# STM_Board.net
KiCad netlist of a schematic drawn in EAGLE
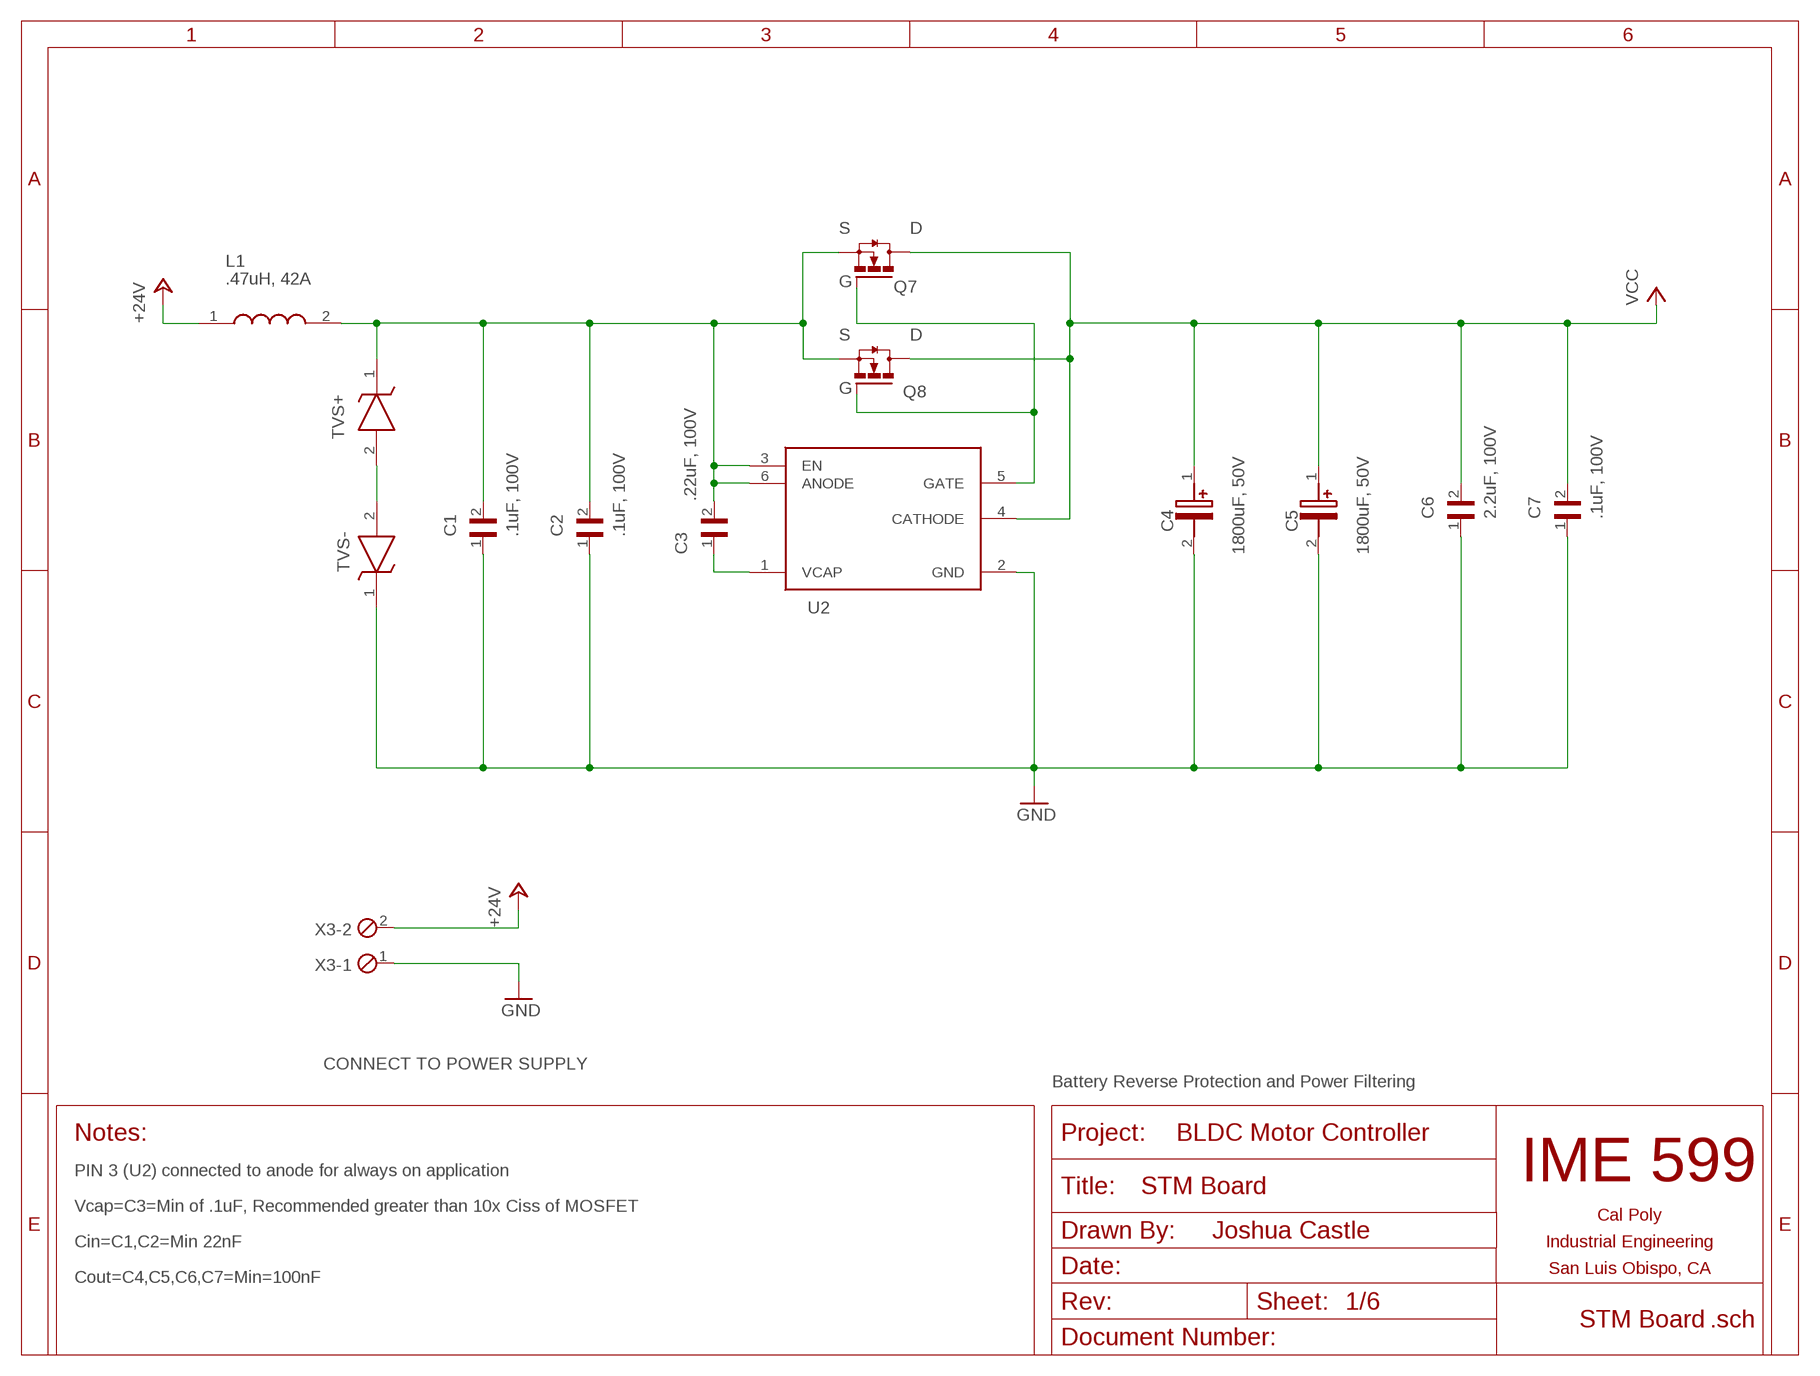
[diagram p0: schematic, sheet 1]
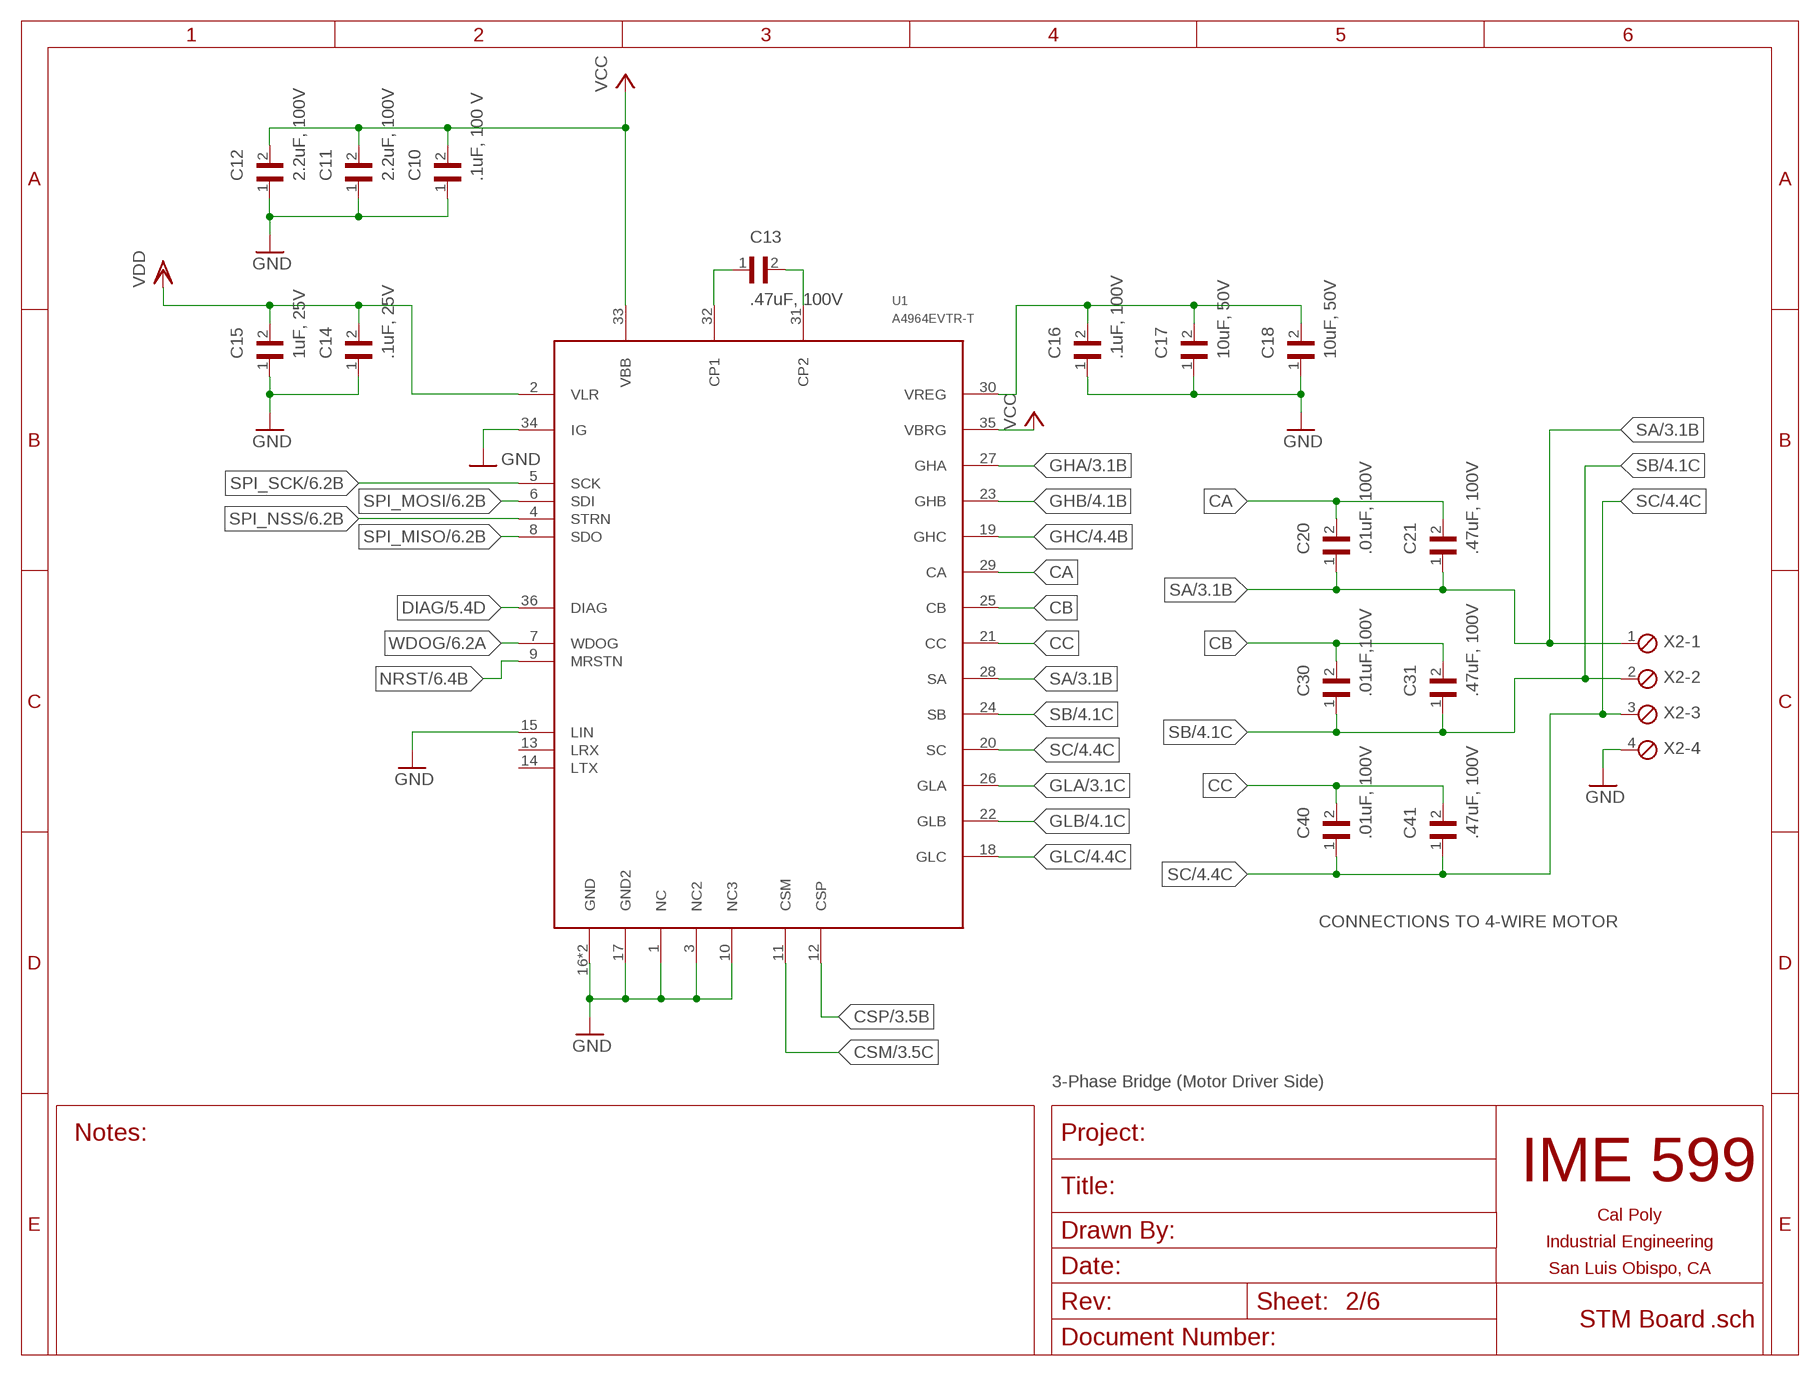
[diagram p1: schematic, sheet 2]
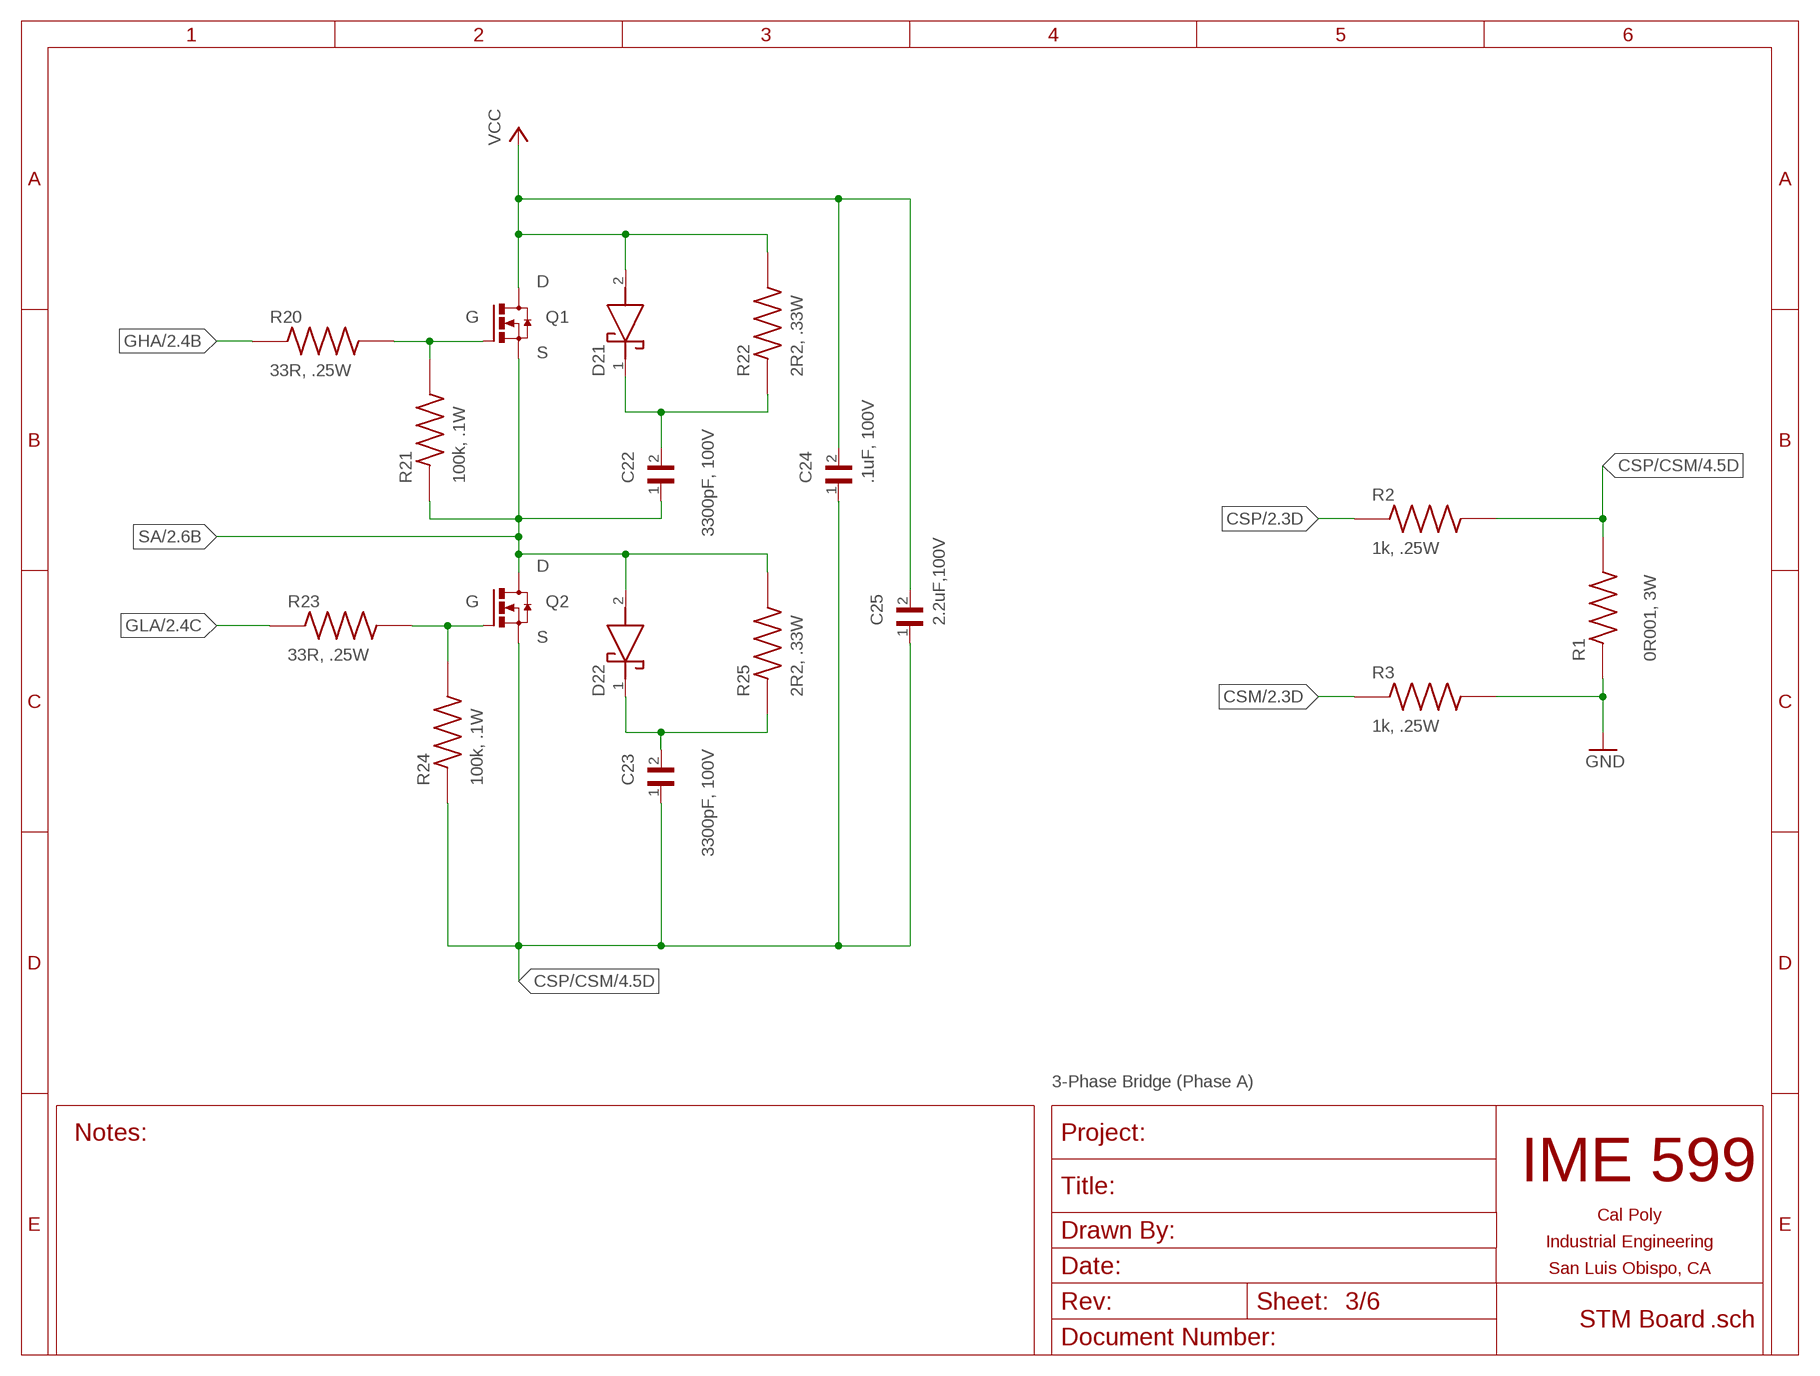
[diagram p2: schematic, sheet 3]
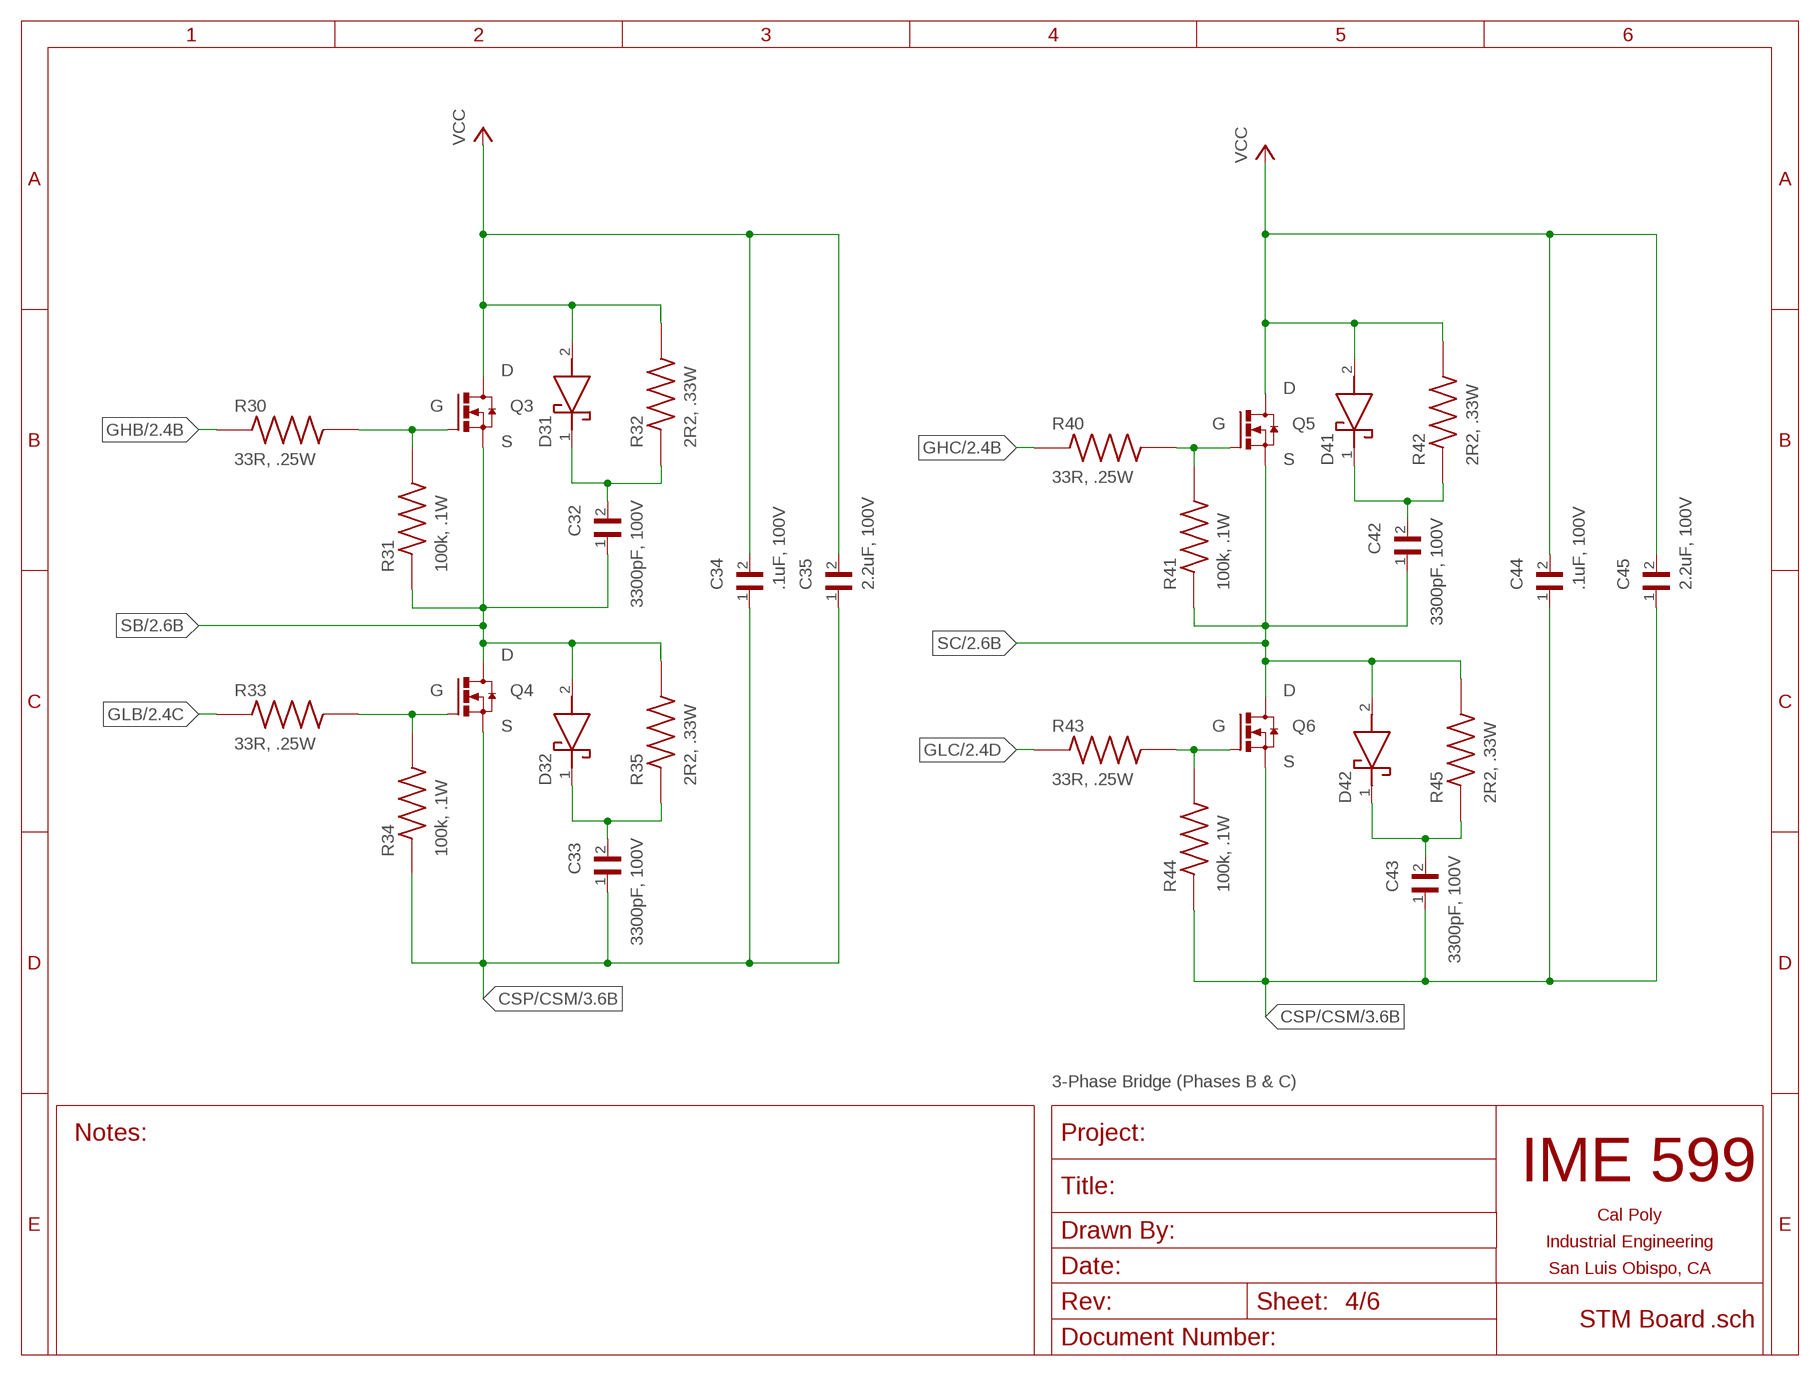
[diagram p3: schematic, sheet 4]
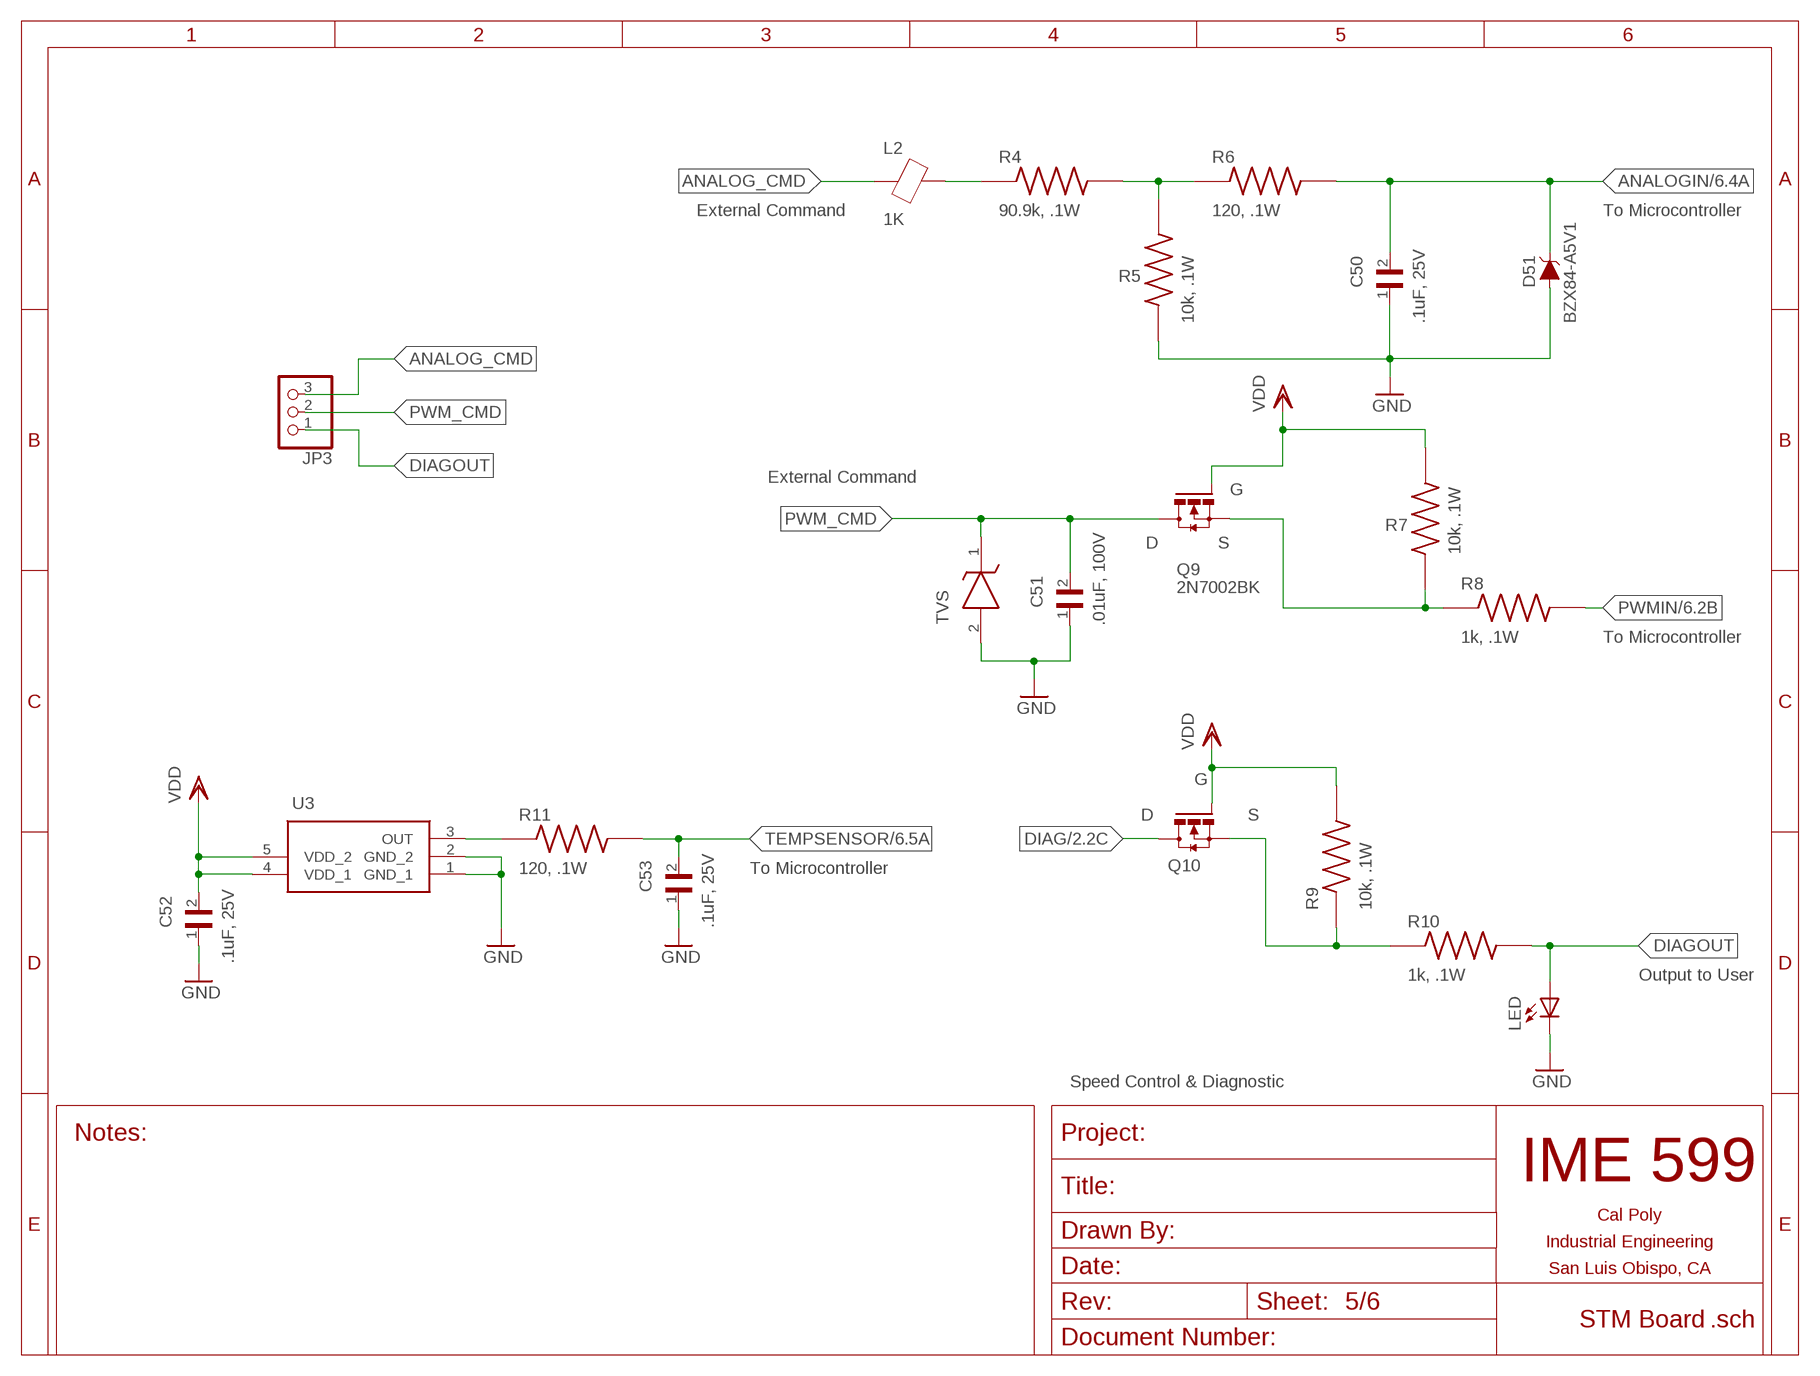
[diagram p4: schematic, sheet 5]
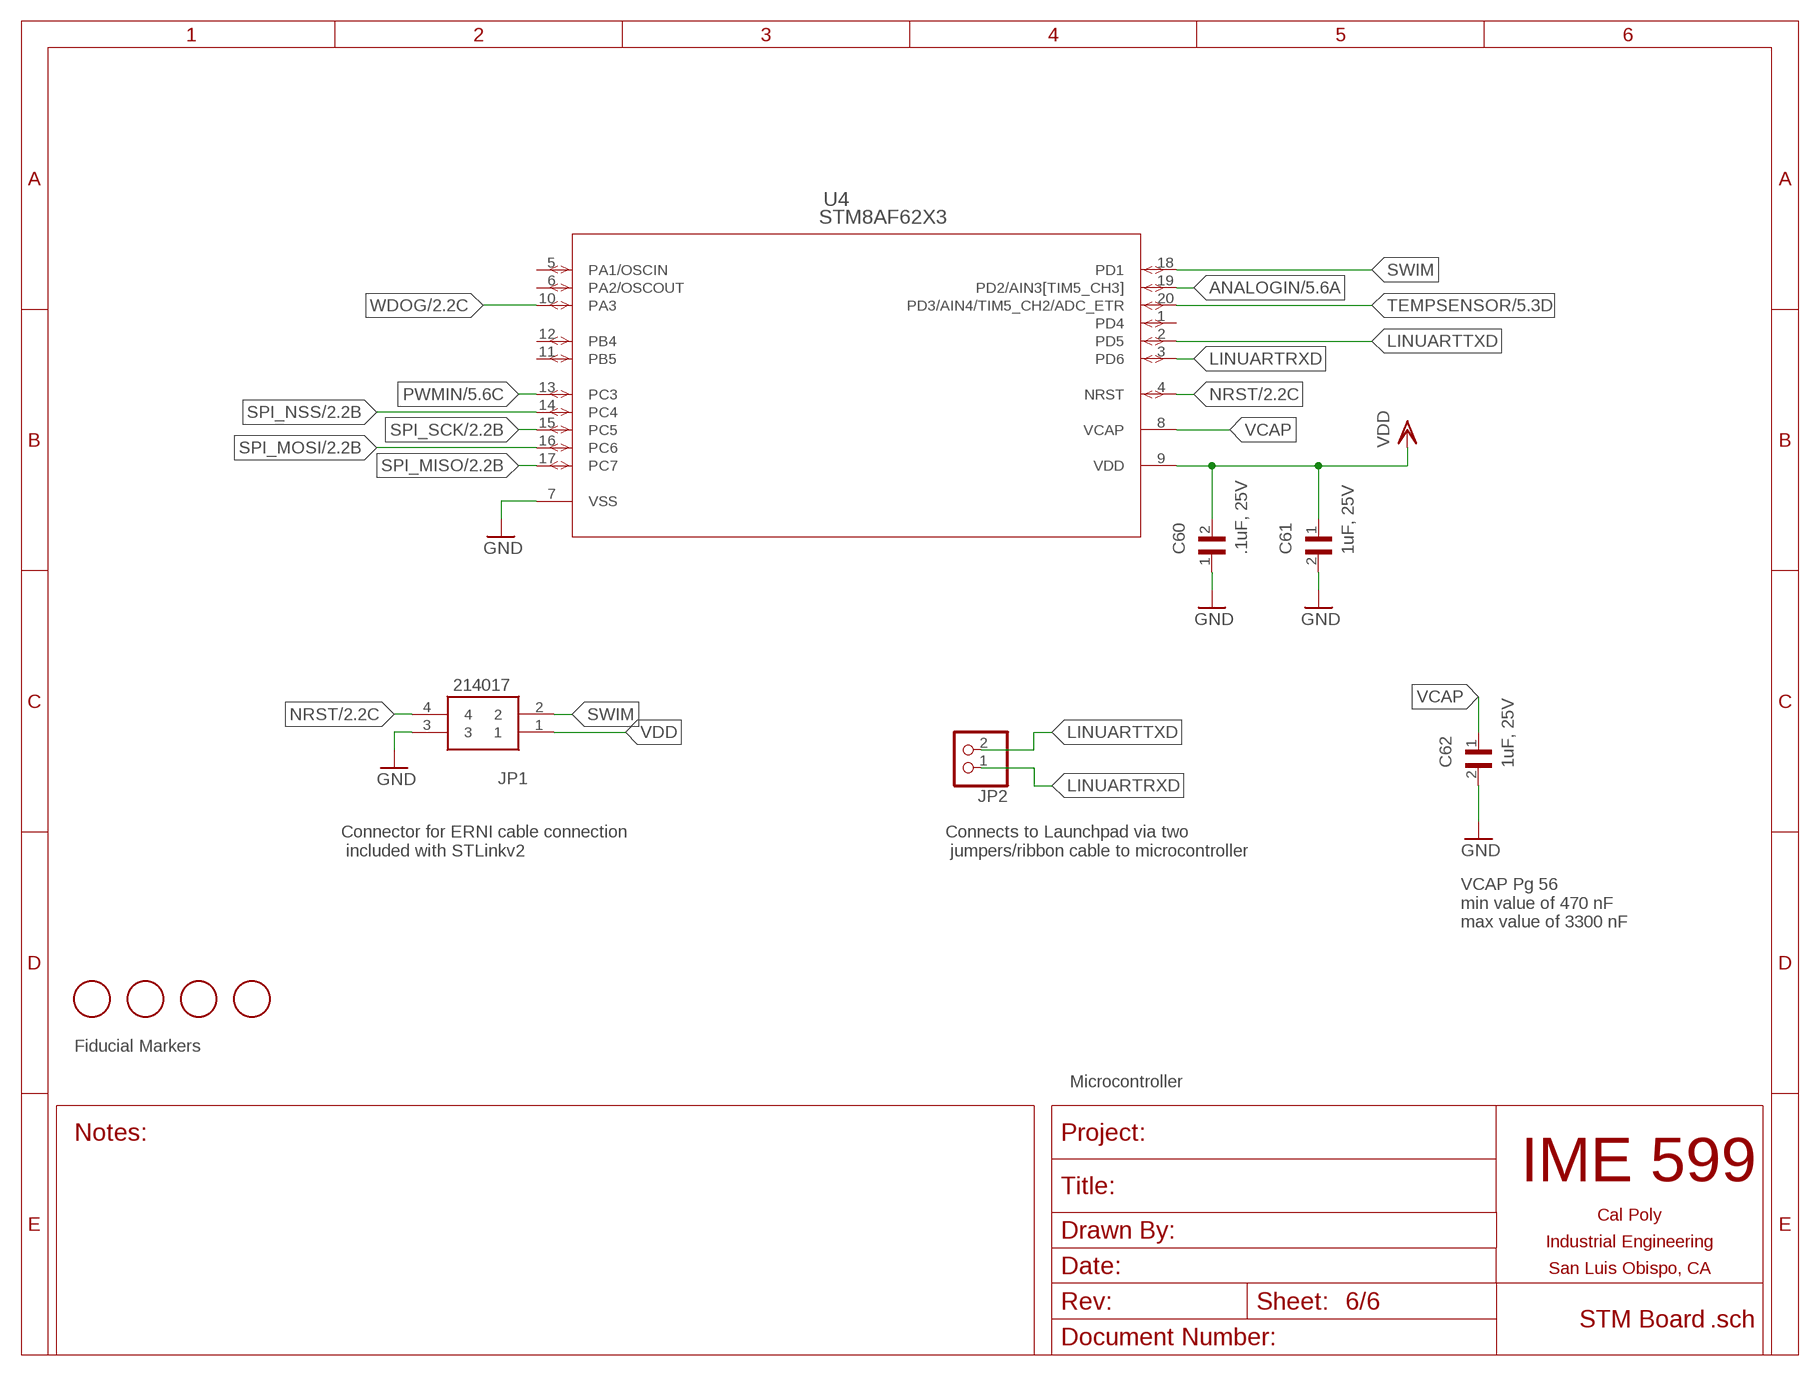
[diagram p5: schematic, sheet 6]

(export (version "E")
  (design (tool "Eeschema 10.0.6"))
  (components
    (comp (ref "C32")
      (value "3300pF, 100V")
      (footprint "eagle-import:CAPC1608X90N")
      (fields
        (field (name "DIGI-KEY_PART_NUMBER") "490-14767-1-ND")
        (field (name "MF") "Murata")
        (field (name "MP") "GCM188R72A332KA37D")
      )
      (libsource (lib "eagle-import") (part "GCM188R72A332KA37D"))
    )
    (comp (ref "C33")
      (value "3300pF, 100V")
      (footprint "eagle-import:CAPC1608X90N")
      (fields
        (field (name "DIGI-KEY_PART_NUMBER") "490-14767-1-ND")
        (field (name "MF") "Murata")
        (field (name "MP") "GCM188R72A332KA37D")
      )
      (libsource (lib "eagle-import") (part "GCM188R72A332KA37D"))
    )
    (comp (ref "C34")
      (value ".1uF, 100V")
      (footprint "eagle-import:CAPC2012X145N")
      (fields
        (field (name "DIGI-KEY_PART_NUMBER") "445-5827-1-ND")
        (field (name "MF") "TDK")
        (field (name "MP") "CGA4J2X7R2A104K125AA")
      )
      (libsource (lib "eagle-import") (part "CGA4J2X7R2A104K125AA"))
    )
    (comp (ref "C35")
      (value "2.2uF, 100V")
      (footprint "eagle-import:CAPC3326X230N")
      (fields
        (field (name "DIGI-KEY_PART_NUMBER") "399-13378-1-ND")
        (field (name "MF") "KEMET")
        (field (name "MP") "C1210X225K1RACAUTO")
      )
      (libsource (lib "eagle-import") (part "C1210X225K1RACAUTO_C1210X225K1RACAUTO"))
    )
    (comp (ref "C42")
      (value "3300pF, 100V")
      (footprint "eagle-import:CAPC1608X90N")
      (fields
        (field (name "DIGI-KEY_PART_NUMBER") "490-14767-1-ND")
        (field (name "MF") "Murata")
        (field (name "MP") "GCM188R72A332KA37D")
      )
      (libsource (lib "eagle-import") (part "GCM188R72A332KA37D"))
    )
    (comp (ref "C43")
      (value "3300pF, 100V")
      (footprint "eagle-import:CAPC1608X90N")
      (fields
        (field (name "DIGI-KEY_PART_NUMBER") "490-14767-1-ND")
        (field (name "MF") "Murata")
        (field (name "MP") "GCM188R72A332KA37D")
      )
      (libsource (lib "eagle-import") (part "GCM188R72A332KA37D"))
    )
    (comp (ref "C44")
      (value ".1uF, 100V")
      (footprint "eagle-import:CAPC2012X145N")
      (fields
        (field (name "DIGI-KEY_PART_NUMBER") "445-5827-1-ND")
        (field (name "MF") "TDK")
        (field (name "MP") "CGA4J2X7R2A104K125AA")
      )
      (libsource (lib "eagle-import") (part "CGA4J2X7R2A104K125AA"))
    )
    (comp (ref "C45")
      (value "2.2uF, 100V")
      (footprint "eagle-import:CAPC3326X230N")
      (fields
        (field (name "DIGI-KEY_PART_NUMBER") "399-13378-1-ND")
        (field (name "MF") "KEMET")
        (field (name "MP") "C1210X225K1RACAUTO")
      )
      (libsource (lib "eagle-import") (part "C1210X225K1RACAUTO_C1210X225K1RACAUTO"))
    )
    (comp (ref "D31")
      (value "PMEG6010EP,115")
      (footprint "eagle-import:SODFL4725X110N")
      (fields (field (name "MOUSER_PART_NUMBER") "771-PMEG6010EP115"))
      (libsource (lib "eagle-import") (part "PMEG6010EP,115"))
    )
    (comp (ref "D32")
      (value "PMEG6010EP,115")
      (footprint "eagle-import:SODFL4725X110N")
      (fields (field (name "MOUSER_PART_NUMBER") "771-PMEG6010EP115"))
      (libsource (lib "eagle-import") (part "PMEG6010EP,115"))
    )
    (comp (ref "D41")
      (value "PMEG6010EP,115")
      (footprint "eagle-import:SODFL4725X110N")
      (fields (field (name "MOUSER_PART_NUMBER") "771-PMEG6010EP115"))
      (libsource (lib "eagle-import") (part "PMEG6010EP,115"))
    )
    (comp (ref "D42")
      (value "PMEG6010EP,115")
      (footprint "eagle-import:SODFL4725X110N")
      (fields (field (name "MOUSER_PART_NUMBER") "771-PMEG6010EP115"))
      (libsource (lib "eagle-import") (part "PMEG6010EP,115"))
    )
    (comp (ref "Q3")
      (value "NVMFS5C604NLAFT1G")
      (footprint "eagle-import:DFN5_5X6(SO-8FL)_CASE-488AA_IS")
      (fields (field (name "MOUSER_PART_NUMBER") "863-NVMFS5C604NLFT1G"))
      (libsource (lib "eagle-import") (part "NVMFS5C604NLAFT1G"))
    )
    (comp (ref "Q4")
      (value "NVMFS5C604NLAFT1G")
      (footprint "eagle-import:DFN5_5X6(SO-8FL)_CASE-488AA_IS")
      (fields (field (name "MOUSER_PART_NUMBER") "863-NVMFS5C604NLFT1G"))
      (libsource (lib "eagle-import") (part "NVMFS5C604NLAFT1G"))
    )
    (comp (ref "Q5")
      (value "NVMFS5C604NLAFT1G")
      (footprint "eagle-import:DFN5_5X6(SO-8FL)_CASE-488AA_IS")
      (fields (field (name "MOUSER_PART_NUMBER") "863-NVMFS5C604NLFT1G"))
      (libsource (lib "eagle-import") (part "NVMFS5C604NLAFT1G"))
    )
    (comp (ref "Q6")
      (value "NVMFS5C604NLAFT1G")
      (footprint "eagle-import:DFN5_5X6(SO-8FL)_CASE-488AA_IS")
      (fields (field (name "MOUSER_PART_NUMBER") "863-NVMFS5C604NLFT1G"))
      (libsource (lib "eagle-import") (part "NVMFS5C604NLAFT1G"))
    )
    (comp (ref "R30")
      (value "33R, .25W")
      (footprint "eagle-import:0805RES")
      (libsource (lib "eagle-import") (part "CRCW060333R0FKEAHP"))
    )
    (comp (ref "R31")
      (value "100k, .1W")
      (footprint "eagle-import:RESC1608X55N")
      (fields (field (name "MF") "Vishay Dale") (field (name "MP") "CRCW0603100KFKEAC"))
      (libsource (lib "eagle-import") (part "CRCW0603100KFKEA"))
    )
    (comp (ref "R32")
      (value "2R2, .33W")
      (footprint "eagle-import:RESC1608X55N")
      (fields
        (field (name "DIGI-KEY_PART_NUMBER") "2019-SG73P1JTTD2R20FTR-ND")
        (field (name "MF") "KOA Speer")
        (field (name "MP") "SG73P1JTTD2R20F")
      )
      (libsource (lib "eagle-import") (part "SG73P1JTTD2R20F"))
    )
    (comp (ref "R33")
      (value "33R, .25W")
      (footprint "eagle-import:0805RES")
      (libsource (lib "eagle-import") (part "CRCW060333R0FKEAHP"))
    )
    (comp (ref "R34")
      (value "100k, .1W")
      (footprint "eagle-import:RESC1608X55N")
      (fields (field (name "MF") "Vishay Dale") (field (name "MP") "CRCW0603100KFKEAC"))
      (libsource (lib "eagle-import") (part "CRCW0603100KFKEA"))
    )
    (comp (ref "R35")
      (value "2R2, .33W")
      (footprint "eagle-import:RESC1608X55N")
      (fields
        (field (name "DIGI-KEY_PART_NUMBER") "2019-SG73P1JTTD2R20FTR-ND")
        (field (name "MF") "KOA Speer")
        (field (name "MP") "SG73P1JTTD2R20F")
      )
      (libsource (lib "eagle-import") (part "SG73P1JTTD2R20F"))
    )
    (comp (ref "R40")
      (value "33R, .25W")
      (footprint "eagle-import:0805RES")
      (libsource (lib "eagle-import") (part "CRCW060333R0FKEAHP"))
    )
    (comp (ref "R41")
      (value "100k, .1W")
      (footprint "eagle-import:RESC1608X55N")
      (fields (field (name "MF") "Vishay Dale") (field (name "MP") "CRCW0603100KFKEAC"))
      (libsource (lib "eagle-import") (part "CRCW0603100KFKEA"))
    )
    (comp (ref "R42")
      (value "2R2, .33W")
      (footprint "eagle-import:RESC1608X55N")
      (fields
        (field (name "DIGI-KEY_PART_NUMBER") "2019-SG73P1JTTD2R20FTR-ND")
        (field (name "MF") "KOA Speer")
        (field (name "MP") "SG73P1JTTD2R20F")
      )
      (libsource (lib "eagle-import") (part "SG73P1JTTD2R20F"))
    )
    (comp (ref "R43")
      (value "33R, .25W")
      (footprint "eagle-import:0805RES")
      (libsource (lib "eagle-import") (part "CRCW060333R0FKEAHP"))
    )
    (comp (ref "R44")
      (value "100k, .1W")
      (footprint "eagle-import:RESC1608X55N")
      (fields (field (name "MF") "Vishay Dale") (field (name "MP") "CRCW0603100KFKEAC"))
      (libsource (lib "eagle-import") (part "CRCW0603100KFKEA"))
    )
    (comp (ref "R45")
      (value "2R2, .33W")
      (footprint "eagle-import:RESC1608X55N")
      (fields
        (field (name "DIGI-KEY_PART_NUMBER") "2019-SG73P1JTTD2R20FTR-ND")
        (field (name "MF") "KOA Speer")
        (field (name "MP") "SG73P1JTTD2R20F")
      )
      (libsource (lib "eagle-import") (part "SG73P1JTTD2R20F"))
    )
    (comp (ref "C50")
      (value ".1uF, 25V")
      (footprint "eagle-import:CAPC1608X90N")
      (fields
        (field (name "DIGI-KEY_PART_NUMBER") "445-5667-1-ND")
        (field (name "MF") "TDK")
        (field (name "MP") "CGA3E2X7R1E104K080AA")
      )
      (libsource (lib "eagle-import") (part "CGA3E2X7R1E104K080AA"))
    )
    (comp (ref "C51")
      (value ".01uF, 100V")
      (footprint "eagle-import:CAPC1608X90N")
      (fields (field (name "MF") "Murata") (field (name "MP") "GCM188R72A223KA37J"))
      (libsource (lib "eagle-import") (part "GCM188R72A223KA37J"))
    )
    (comp (ref "C52")
      (value ".1uF, 25V")
      (footprint "eagle-import:CAPC1608X90N")
      (fields
        (field (name "DIGI-KEY_PART_NUMBER") "445-5667-1-ND")
        (field (name "MF") "TDK")
        (field (name "MP") "CGA3E2X7R1E104K080AA")
      )
      (libsource (lib "eagle-import") (part "CGA3E2X7R1E104K080AA"))
    )
    (comp (ref "C53")
      (value ".1uF, 25V")
      (footprint "eagle-import:CAPC1608X90N")
      (fields
        (field (name "DIGI-KEY_PART_NUMBER") "445-5667-1-ND")
        (field (name "MF") "TDK")
        (field (name "MP") "CGA3E2X7R1E104K080AA")
      )
      (libsource (lib "eagle-import") (part "CGA3E2X7R1E104K080AA"))
    )
    (comp (ref "D51")
      (value "BZX84-A5V1")
      (footprint "eagle-import:SOT95P230X110-3N")
      (fields
        (field (name "FARNELL_PART_NUMBER") "2345405")
        (field (name "MANUFACTURER_PART_NUMBER") "BZX84-A5V1,215")
      )
      (libsource (lib "eagle-import") (part "BZX84-A5V1,215"))
    )
    (comp (ref "JP3")
      (value "PINHD-1X3")
      (footprint "eagle-import:1X03")
      (libsource (lib "eagle-import") (part "PINHD-1X3"))
    )
    (comp (ref "L2")
      (value "1K")
      (footprint "eagle-import:BEADC1608X95N")
      (libsource (lib "eagle-import") (part "KMZ1608RHR102ATD25"))
    )
    (comp (ref "LED")
      (value "LTST-C170KRKT")
      (footprint "eagle-import:DIOC200X125X110")
      (fields (field (name "DIGI-KEY_PART_NUMBER") "160-1415-1-ND") (field (name "MF") "Lite-On Inc."))
      (libsource (lib "eagle-import") (part "LTST-C170KRKT"))
    )
    (comp (ref "Q9")
      (value "2N7002BK")
      (footprint "eagle-import:2N7002BK")
      (libsource (lib "eagle-import") (part "2N002BK"))
    )
    (comp (ref "Q10")
      (value "BSS123N_H6327")
      (footprint "eagle-import:BSS123N_H6327")
      (libsource (lib "eagle-import") (part "BSS123N_H6327"))
    )
    (comp (ref "R4")
      (value "90.9k, .1W")
      (footprint "eagle-import:CAPC1608X90N")
      (libsource (lib "eagle-import") (part "CRCW060318K0FK"))
    )
    (comp (ref "R5")
      (value "10k, .1W")
      (footprint "eagle-import:CAPC1608X90N")
      (libsource (lib "eagle-import") (part "CRCW060322K0FK"))
    )
    (comp (ref "R6")
      (value "120, .1W")
      (footprint "eagle-import:CAPC1608X90N")
      (libsource (lib "eagle-import") (part "CRCW0603120RFK"))
    )
    (comp (ref "R7")
      (value "10k, .1W")
      (footprint "eagle-import:RESC1508X50N")
      (fields (field (name "MF") "Vishay Dale") (field (name "MP") "CRCW060310K0FKEB"))
      (libsource (lib "eagle-import") (part "CRCW060310K0FKEB"))
    )
    (comp (ref "R8")
      (value "1k, .1W")
      (footprint "eagle-import:RESC1508X50N")
      (fields (field (name "MF") "Vishay") (field (name "MP") "CRCW06031K00FKEA"))
      (libsource (lib "eagle-import") (part "CRCW06031K00FKEA"))
    )
    (comp (ref "R9")
      (value "10k, .1W")
      (footprint "eagle-import:RESC1508X50N")
      (fields (field (name "MF") "Vishay Dale") (field (name "MP") "CRCW060310K0FKEB"))
      (libsource (lib "eagle-import") (part "CRCW060310K0FKEB"))
    )
    (comp (ref "R10")
      (value "1k, .1W")
      (footprint "eagle-import:RESC1508X50N")
      (fields (field (name "MF") "Vishay") (field (name "MP") "CRCW06031K00FKEA"))
      (libsource (lib "eagle-import") (part "CRCW06031K00FKEA"))
    )
    (comp (ref "R11")
      (value "120, .1W")
      (footprint "eagle-import:CAPC1608X90N")
      (libsource (lib "eagle-import") (part "CRCW0603120RFK"))
    )
    (comp (ref "TVS")
      (value "SMBJ30AQ-13-F")
      (footprint "eagle-import:DIOM5336X250N")
      (fields (field (name "MOUSER_PART_NUMBER") "621-SMBJ30AQ-13-F"))
      (libsource (lib "eagle-import") (part "SMBJ30AQ-13-F"))
    )
    (comp (ref "U3")
      (value "LMT86QDCKRQ1")
      (footprint "eagle-import:SOT65P210X110-5N")
      (fields (field (name "MOUSER_PART_NUMBER") "595-LMT86QDCKRQ1"))
      (libsource (lib "eagle-import") (part "LMT86QDCKRQ1"))
    )
    (comp (ref "C60")
      (value ".1uF, 25V")
      (footprint "eagle-import:CAPC1608X90N")
      (fields
        (field (name "DIGI-KEY_PART_NUMBER") "445-5667-1-ND")
        (field (name "MF") "TDK")
        (field (name "MP") "CGA3E2X7R1E104K080AA")
      )
      (libsource (lib "eagle-import") (part "CGA3E2X7R1E104K080AA"))
    )
    (comp (ref "C61")
      (value "1uF, 25V")
      (footprint "eagle-import:CAPC2012X88N")
      (fields
        (field (name "DIGI-KEY_PART_NUMBER") "399-6929-1-ND")
        (field (name "MF") "KEMET")
        (field (name "MP") "C0805C105K3RACAUTO")
      )
      (libsource (lib "eagle-import") (part "C0805C105K3RACAUTO"))
    )
    (comp (ref "C62")
      (value "1uF, 25V")
      (footprint "eagle-import:CAPC2012X88N")
      (fields
        (field (name "DIGI-KEY_PART_NUMBER") "399-6929-1-ND")
        (field (name "MF") "KEMET")
        (field (name "MP") "C0805C105K3RACAUTO")
      )
      (libsource (lib "eagle-import") (part "C0805C105K3RACAUTO"))
    )
    (comp (ref "JP1")
      (value "214017")
      (footprint "eagle-import:214017")
      (fields (field (name "MOUSER_PART_NUMBER") "305-214017"))
      (libsource (lib "eagle-import") (part "214017"))
    )
    (comp (ref "JP2")
      (value "PINHD-1X2")
      (footprint "eagle-import:1X02")
      (libsource (lib "eagle-import") (part "PINHD-1X2"))
    )
    (comp (ref "U$1")
      (value "FIDUCIAL")
      (footprint "eagle-import:FIDUCIAL_1MM")
      (libsource (lib "eagle-import") (part "FIDUCIAL"))
    )
    (comp (ref "U$2")
      (value "FIDUCIAL")
      (footprint "eagle-import:FIDUCIAL_1MM")
      (libsource (lib "eagle-import") (part "FIDUCIAL"))
    )
    (comp (ref "U$3")
      (value "FIDUCIAL")
      (footprint "eagle-import:FIDUCIAL_1MM")
      (libsource (lib "eagle-import") (part "FIDUCIAL"))
    )
    (comp (ref "U$4")
      (value "FIDUCIAL")
      (footprint "eagle-import:FIDUCIAL_1MM")
      (libsource (lib "eagle-import") (part "FIDUCIAL"))
    )
    (comp (ref "U4")
      (value "STM8AF62X3")
      (footprint "eagle-import:TSSOP20")
      (fields (field (name "COPYRIGHT") "Copyright (C) 2016 Accelerated Designs. All rights reserved"))
      (libsource (lib "eagle-import") (part "STM8AF62X3"))
    )
    (comp (ref "C10")
      (value ".1uF, 100 V")
      (footprint "eagle-import:CAPC2012X145N")
      (fields
        (field (name "DIGI-KEY_PART_NUMBER") "445-5827-1-ND")
        (field (name "MF") "TDK")
        (field (name "MP") "CGA4J2X7R2A104K125AA")
      )
      (libsource (lib "eagle-import") (part "CGA4J2X7R2A104K125AA"))
    )
    (comp (ref "C11")
      (value "2.2uF, 100V")
      (footprint "eagle-import:CAPC3326X230N")
      (fields
        (field (name "DIGI-KEY_PART_NUMBER") "399-13378-1-ND")
        (field (name "MF") "KEMET")
        (field (name "MP") "C1210X225K1RACAUTO")
      )
      (libsource (lib "eagle-import") (part "C1210X225K1RACAUTO_C1210X225K1RACAUTO"))
    )
    (comp (ref "C12")
      (value "2.2uF, 100V")
      (footprint "eagle-import:CAPC3326X230N")
      (fields
        (field (name "DIGI-KEY_PART_NUMBER") "399-13378-1-ND")
        (field (name "MF") "KEMET")
        (field (name "MP") "C1210X225K1RACAUTO")
      )
      (libsource (lib "eagle-import") (part "C1210X225K1RACAUTO_C1210X225K1RACAUTO"))
    )
    (comp (ref "C13")
      (value ".47uF, 100V")
      (footprint "eagle-import:CAPC2012X140N")
      (fields
        (field (name "DIGI-KEY_PART_NUMBER") "478-10684-1-ND")
        (field (name "MF") "AVX")
        (field (name "MP") "08051C474K4T2A")
      )
      (libsource (lib "eagle-import") (part "08051C474K4T2A"))
    )
    (comp (ref "C14")
      (value ".1uF, 25V")
      (footprint "eagle-import:CAPC1608X90N")
      (fields
        (field (name "DIGI-KEY_PART_NUMBER") "445-5667-1-ND")
        (field (name "MF") "TDK")
        (field (name "MP") "CGA3E2X7R1E104K080AA")
      )
      (libsource (lib "eagle-import") (part "CGA3E2X7R1E104K080AA"))
    )
    (comp (ref "C15")
      (value "1uF, 25V")
      (footprint "eagle-import:CAPC2012X140N")
      (fields (field (name "MF") "Murata") (field (name "MP") "GCM21BR71H105KA03K"))
      (libsource (lib "eagle-import") (part "GCM21BR71H105KA03K"))
    )
    (comp (ref "C16")
      (value ".1uF, 100V")
      (footprint "eagle-import:CAPC2012X145N")
      (fields (field (name "MF") "TDK") (field (name "MP") "CGA4J2X7R1E474K125AA"))
      (libsource (lib "eagle-import") (part "CGA4J2X7R1E474K125AA"))
    )
    (comp (ref "C17")
      (value "10uF, 50V")
      (footprint "eagle-import:CAPC3225X280N")
      (fields
        (field (name "DIGI-KEY_PART_NUMBER") "587-6026-1-ND")
        (field (name "MF") "Taiyo Yuden")
        (field (name "MP") "UMJ325KB7106KMHP")
      )
      (libsource (lib "eagle-import") (part "UMJ325KB7106KMHP"))
    )
    (comp (ref "C18")
      (value "10uF, 50V")
      (footprint "eagle-import:CAPC3225X280N")
      (fields
        (field (name "DIGI-KEY_PART_NUMBER") "587-6026-1-ND")
        (field (name "MF") "Taiyo Yuden")
        (field (name "MP") "UMJ325KB7106KMHP")
      )
      (libsource (lib "eagle-import") (part "UMJ325KB7106KMHP"))
    )
    (comp (ref "C20")
      (value ".01uF, 100V")
      (footprint "eagle-import:CAPC1608X90N")
      (fields
        (field (name "DIGI-KEY_PART_NUMBER") "490-4781-1-ND")
        (field (name "MF") "Murata")
        (field (name "MP") "GCM188R72A103KA37D")
      )
      (libsource (lib "eagle-import") (part "GCM188R72A103KA37D"))
    )
    (comp (ref "C21")
      (value ".47uF, 100V")
      (footprint "eagle-import:CAPC2012X140N")
      (fields
        (field (name "DIGI-KEY_PART_NUMBER") "478-10684-1-ND")
        (field (name "MF") "AVX")
        (field (name "MP") "08051C474K4T2A")
      )
      (libsource (lib "eagle-import") (part "08051C474K4T2A"))
    )
    (comp (ref "C30")
      (value ".01uF,100V")
      (footprint "eagle-import:CAPC1608X90N")
      (fields
        (field (name "DIGI-KEY_PART_NUMBER") "490-4781-1-ND")
        (field (name "MF") "Murata")
        (field (name "MP") "GCM188R72A103KA37D")
      )
      (libsource (lib "eagle-import") (part "GCM188R72A103KA37D"))
    )
    (comp (ref "C31")
      (value ".47uF, 100V")
      (footprint "eagle-import:CAPC2012X140N")
      (fields
        (field (name "DIGI-KEY_PART_NUMBER") "478-10684-1-ND")
        (field (name "MF") "AVX")
        (field (name "MP") "08051C474K4T2A")
      )
      (libsource (lib "eagle-import") (part "08051C474K4T2A"))
    )
    (comp (ref "C40")
      (value ".01uF, 100V")
      (footprint "eagle-import:CAPC1608X90N")
      (fields
        (field (name "DIGI-KEY_PART_NUMBER") "490-4781-1-ND")
        (field (name "MF") "Murata")
        (field (name "MP") "GCM188R72A103KA37D")
      )
      (libsource (lib "eagle-import") (part "GCM188R72A103KA37D"))
    )
    (comp (ref "C41")
      (value ".47uF, 100V")
      (footprint "eagle-import:CAPC2012X140N")
      (fields
        (field (name "DIGI-KEY_PART_NUMBER") "478-10684-1-ND")
        (field (name "MF") "AVX")
        (field (name "MP") "08051C474K4T2A")
      )
      (libsource (lib "eagle-import") (part "08051C474K4T2A"))
    )
    (comp (ref "U1")
      (value "A4964EVTR-T")
      (footprint "eagle-import:A4964EVTR-T")
      (libsource (lib "eagle-import") (part "A4964EVTR-T"))
    )
    (comp (ref "X2")
      (value "SCREWTERM_4P_254")
      (footprint "eagle-import:4POL254")
      (libsource (lib "eagle-import") (part "SCREWTERM_4P_254"))
    )
    (comp (ref "C1")
      (value ".1uF, 100V")
      (footprint "eagle-import:CAPC2012X145N")
      (fields (field (name "MF") "TDK") (field (name "MP") "CGA4J2X7R1E474K125AA"))
      (libsource (lib "eagle-import") (part "CGA4J2X7R1E474K125AA"))
    )
    (comp (ref "C2")
      (value ".1uF, 100V")
      (footprint "eagle-import:CAPC2012X145N")
      (fields (field (name "MF") "TDK") (field (name "MP") "CGA4J2X7R1E474K125AA"))
      (libsource (lib "eagle-import") (part "CGA4J2X7R1E474K125AA"))
    )
    (comp (ref "C3")
      (value ".22uF, 100V")
      (footprint "eagle-import:CAPC2012X140N")
      (fields
        (field (name "DIGI-KEY_PART_NUMBER") "399-17890-1-ND")
        (field (name "MF") "KEMET")
        (field (name "MP") "C0805C224K1RECAUTO")
      )
      (libsource (lib "eagle-import") (part "C0805C224K1RECAUTO"))
    )
    (comp (ref "C4")
      (value "1800uF, 50V")
      (footprint "eagle-import:CAPPRD750W80D1475H4150(HORIZONTAL)")
      (libsource (lib "eagle-import") (part "EGPA500ELL182MU40S(HORIZONTAL)"))
    )
    (comp (ref "C5")
      (value "1800uF, 50V")
      (footprint "eagle-import:CAPPRD750W80D1475H4150(HORIZONTAL)")
      (libsource (lib "eagle-import") (part "EGPA500ELL182MU40S(HORIZONTAL)"))
    )
    (comp (ref "C6")
      (value "2.2uF, 100V")
      (footprint "eagle-import:CAPC3326X230N")
      (fields
        (field (name "DIGI-KEY_PART_NUMBER") "399-13378-1-ND")
        (field (name "MF") "KEMET")
        (field (name "MP") "C1210X225K1RACAUTO")
      )
      (libsource (lib "eagle-import") (part "C1210X225K1RACAUTO"))
    )
    (comp (ref "C7")
      (value ".1uF, 100V")
      (footprint "eagle-import:CAPC2012X145N")
      (fields
        (field (name "DIGI-KEY_PART_NUMBER") "445-5827-1-ND")
        (field (name "MF") "TDK")
        (field (name "MP") "CGA4J2X7R2A104K125AA")
      )
      (libsource (lib "eagle-import") (part "CGA4J2X7R2A104K125AA"))
    )
    (comp (ref "L1")
      (value ".47uH, 42A")
      (footprint "eagle-import:HCM1A1305V2R47R")
      (fields
        (field (name "MANUFACTURER_PART_NUMBER") "HCM1A1305V2-R47-R")
        (field (name "MOUSER_PART_NUMBER") "504-HCM1A1305V2R47-R")
      )
      (libsource (lib "eagle-import") (part "HCM1A1305V2-R47-R"))
    )
    (comp (ref "Q7")
      (value "FDBL86361-F085")
      (footprint "eagle-import:H-PSOF8L-11.68X9.80_1")
      (fields (field (name "MOUSER_PART_NUMBER") "512-FDBL86361F085"))
      (libsource (lib "eagle-import") (part "FDBL86361-F085"))
    )
    (comp (ref "Q8")
      (value "FDBL86361-F085")
      (footprint "eagle-import:H-PSOF8L-11.68X9.80_1")
      (fields (field (name "MOUSER_PART_NUMBER") "512-FDBL86361F085"))
      (libsource (lib "eagle-import") (part "FDBL86361-F085"))
    )
    (comp (ref "TVS+")
      (value "SMBJ58A-Q")
      (footprint "eagle-import:DIOM5436X244N")
      (fields (field (name "MOUSER_PART_NUMBER") "652-SMBJ58A-Q"))
      (libsource (lib "eagle-import") (part "SMBJ58A-Q"))
    )
    (comp (ref "TVS-")
      (value "SMBJ26A-Q")
      (footprint "eagle-import:DIOM5436X244N")
      (fields (field (name "MOUSER_PART_NUMBER") "652-SMBJ26A-Q"))
      (libsource (lib "eagle-import") (part "SMBJ26A-Q"))
    )
    (comp (ref "U2")
      (value "LM74700-Q1MKX-1_NOPB")
      (footprint "eagle-import:SOT95P280X145-6N")
      (fields (field (name "MANUFACTURER_PART_NUMBER") "LM74700-Q1MKX-1/NOPB"))
      (libsource (lib "eagle-import") (part "LM74700-Q1MKX-1_NOPB"))
    )
    (comp (ref "X3")
      (value "SCREWTERM_2P_254")
      (footprint "eagle-import:2POL254")
      (libsource (lib "eagle-import") (part "SCREWTERM_2P_254"))
    )
    (comp (ref "C22")
      (value "3300pF, 100V")
      (footprint "eagle-import:CAPC1608X90N")
      (fields
        (field (name "DIGI-KEY_PART_NUMBER") "490-14767-1-ND")
        (field (name "MF") "Murata")
        (field (name "MP") "GCM188R72A332KA37D")
      )
      (libsource (lib "eagle-import") (part "GCM188R72A332KA37D"))
    )
    (comp (ref "C23")
      (value "3300pF, 100V")
      (footprint "eagle-import:CAPC1608X90N")
      (fields
        (field (name "DIGI-KEY_PART_NUMBER") "490-14767-1-ND")
        (field (name "MF") "Murata")
        (field (name "MP") "GCM188R72A332KA37D")
      )
      (libsource (lib "eagle-import") (part "GCM188R72A332KA37D"))
    )
    (comp (ref "C24")
      (value ".1uF, 100V")
      (footprint "eagle-import:CAPC2012X145N")
      (fields (field (name "MF") "TDK") (field (name "MP") "CGA4J2X7R1E474K125AA"))
      (libsource (lib "eagle-import") (part "CGA4J2X7R1E474K125AA"))
    )
    (comp (ref "C25")
      (value "2.2uF,100V")
      (footprint "eagle-import:CAPC3326X230N")
      (fields
        (field (name "DIGI-KEY_PART_NUMBER") "399-13378-1-ND")
        (field (name "MF") "KEMET")
        (field (name "MP") "C1210X225K1RACAUTO")
      )
      (libsource (lib "eagle-import") (part "C1210X225K1RACAUTO_C1210X225K1RACAUTO"))
    )
    (comp (ref "D21")
      (value "PMEG6010EP,115")
      (footprint "eagle-import:SODFL4725X110N")
      (fields (field (name "MOUSER_PART_NUMBER") "771-PMEG6010EP115"))
      (libsource (lib "eagle-import") (part "PMEG6010EP,115"))
    )
    (comp (ref "D22")
      (value "PMEG6010EP,115")
      (footprint "eagle-import:SODFL4725X110N")
      (fields (field (name "MOUSER_PART_NUMBER") "771-PMEG6010EP115"))
      (libsource (lib "eagle-import") (part "PMEG6010EP,115"))
    )
    (comp (ref "Q1")
      (value "NVMFS5C604NLAFT1G")
      (footprint "eagle-import:DFN5_5X6(SO-8FL)_CASE-488AA_IS")
      (fields (field (name "MOUSER_PART_NUMBER") "863-NVMFS5C604NLFT1G"))
      (libsource (lib "eagle-import") (part "NVMFS5C604NLAFT1G"))
    )
    (comp (ref "Q2")
      (value "NVMFS5C604NLAFT1G")
      (footprint "eagle-import:DFN5_5X6(SO-8FL)_CASE-488AA_IS")
      (fields (field (name "MOUSER_PART_NUMBER") "863-NVMFS5C604NLFT1G"))
      (libsource (lib "eagle-import") (part "NVMFS5C604NLAFT1G"))
    )
    (comp (ref "R1")
      (value "0R001, 3W")
      (footprint "eagle-import:RESC6432X90N")
      (fields
        (field (name "DIGI-KEY_PART_NUMBER") "CRA2512-FZ-R100ELFCT-ND")
        (field (name "MF") "Bourns")
        (field (name "MP") "CRA2512-FZ-R100ELF")
      )
      (libsource (lib "eagle-import") (part "CRA2512-FZ-R100ELF"))
    )
    (comp (ref "R2")
      (value "1k, .25W")
      (footprint "eagle-import:RESC1608X55N")
      (fields (field (name "MF") "Rohm") (field (name "MP") "ESR03EZPF1001"))
      (libsource (lib "eagle-import") (part "ESR03EZPF1001"))
    )
    (comp (ref "R3")
      (value "1k, .25W")
      (footprint "eagle-import:RESC1608X55N")
      (fields (field (name "MF") "Rohm") (field (name "MP") "ESR03EZPF1001"))
      (libsource (lib "eagle-import") (part "ESR03EZPF1001"))
    )
    (comp (ref "R20")
      (value "33R, .25W")
      (footprint "eagle-import:0805RES")
      (libsource (lib "eagle-import") (part "CRCW060333R0FKEAHP"))
    )
    (comp (ref "R21")
      (value "100k, .1W")
      (footprint "eagle-import:RESC1508X50N")
      (fields (field (name "MF") "Vishay") (field (name "MP") "CRCW06031K00FKEA"))
      (libsource (lib "eagle-import") (part "CRCW06031K00FKEA"))
    )
    (comp (ref "R22")
      (value "2R2, .33W")
      (footprint "eagle-import:RESC1608X55N")
      (fields
        (field (name "DIGI-KEY_PART_NUMBER") "2019-SG73P1JTTD2R20FTR-ND")
        (field (name "MF") "KOA Speer")
        (field (name "MP") "SG73P1JTTD2R20F")
      )
      (libsource (lib "eagle-import") (part "SG73P1JTTD2R20F"))
    )
    (comp (ref "R23")
      (value "33R, .25W")
      (footprint "eagle-import:0805RES")
      (libsource (lib "eagle-import") (part "CRCW060333R0FKEAHP"))
    )
    (comp (ref "R24")
      (value "100k, .1W")
      (footprint "eagle-import:RESC1508X50N")
      (fields (field (name "MF") "Vishay") (field (name "MP") "CRCW06031K00FKEA"))
      (libsource (lib "eagle-import") (part "CRCW06031K00FKEA"))
    )
    (comp (ref "R25")
      (value "2R2, .33W")
      (footprint "eagle-import:RESC1608X55N")
      (fields
        (field (name "DIGI-KEY_PART_NUMBER") "2019-SG73P1JTTD2R20FTR-ND")
        (field (name "MF") "KOA Speer")
        (field (name "MP") "SG73P1JTTD2R20F")
      )
      (libsource (lib "eagle-import") (part "SG73P1JTTD2R20F"))
    )
  )
  (nets
    (net (code "1") (name "+24V") (class "Default")
      (node (ref "L1") (pin "1") (pinfunction "1_1") (pintype "bidirectional"))
      (node (ref "X3") (pin "2") (pinfunction "1_2") (pintype "passive"))
    )
    (net (code "2") (name "ANALOGIN") (class "Default")
      (node (ref "C50") (pin "2") (pinfunction "2_2") (pintype "passive"))
      (node (ref "D51") (pin "3") (pinfunction "C_3") (pintype "passive"))
      (node (ref "R6") (pin "2") (pinfunction "2_2") (pintype "passive"))
      (node (ref "U4") (pin "19") (pinfunction "PD2/AIN3[TIM5_CH3]_19") (pintype "bidirectional"))
    )
    (net (code "3") (name "ANALOG_CMD") (class "Default")
      (node (ref "JP3") (pin "3") (pinfunction "3_3") (pintype "passive"))
      (node (ref "L2") (pin "1") (pinfunction "1_1") (pintype "bidirectional"))
    )
    (net (code "4") (name "CA") (class "Default")
      (node (ref "C20") (pin "2") (pinfunction "2_2") (pintype "passive"))
      (node (ref "C21") (pin "2") (pinfunction "2_2") (pintype "passive"))
      (node (ref "U1") (pin "29") (pinfunction "CA_29") (pintype "bidirectional"))
    )
    (net (code "5") (name "CB") (class "Default")
      (node (ref "C30") (pin "2") (pinfunction "2_2") (pintype "passive"))
      (node (ref "C31") (pin "2") (pinfunction "2_2") (pintype "passive"))
      (node (ref "U1") (pin "25") (pinfunction "CB_25") (pintype "bidirectional"))
    )
    (net (code "6") (name "CC") (class "Default")
      (node (ref "C40") (pin "2") (pinfunction "2_2") (pintype "passive"))
      (node (ref "C41") (pin "2") (pinfunction "2_2") (pintype "passive"))
      (node (ref "U1") (pin "21") (pinfunction "CC_21") (pintype "bidirectional"))
    )
    (net (code "7") (name "CSM") (class "Default")
      (node (ref "R3") (pin "1") (pinfunction "1_1") (pintype "passive"))
      (node (ref "U1") (pin "11") (pinfunction "CSM_11") (pintype "bidirectional"))
    )
    (net (code "8") (name "CSP") (class "Default")
      (node (ref "R2") (pin "1") (pinfunction "1_1") (pintype "passive"))
      (node (ref "U1") (pin "12") (pinfunction "CSP_12") (pintype "bidirectional"))
    )
    (net (code "9") (name "CSP{slash}CSM") (class "Default")
      (node (ref "C23") (pin "1") (pinfunction "1_1") (pintype "passive"))
      (node (ref "C24") (pin "1") (pinfunction "1_1") (pintype "passive"))
      (node (ref "C25") (pin "1") (pinfunction "1_1") (pintype "passive"))
      (node (ref "C33") (pin "1") (pinfunction "1_1") (pintype "passive"))
      (node (ref "C34") (pin "1") (pinfunction "1_1") (pintype "passive"))
      (node (ref "C35") (pin "1") (pinfunction "1_1") (pintype "passive"))
      (node (ref "C43") (pin "1") (pinfunction "1_1") (pintype "passive"))
      (node (ref "C44") (pin "1") (pinfunction "1_1") (pintype "passive"))
      (node (ref "C45") (pin "1") (pinfunction "1_1") (pintype "passive"))
      (node (ref "Q2") (pin "1") (pinfunction "S_1") (pintype "passive"))
      (node (ref "Q2") (pin "2") (pinfunction "S_2") (pintype "passive"))
      (node (ref "Q2") (pin "3") (pinfunction "S_3") (pintype "passive"))
      (node (ref "Q4") (pin "1") (pinfunction "S_1") (pintype "passive"))
      (node (ref "Q4") (pin "2") (pinfunction "S_2") (pintype "passive"))
      (node (ref "Q4") (pin "3") (pinfunction "S_3") (pintype "passive"))
      (node (ref "Q6") (pin "1") (pinfunction "S_1") (pintype "passive"))
      (node (ref "Q6") (pin "2") (pinfunction "S_2") (pintype "passive"))
      (node (ref "Q6") (pin "3") (pinfunction "S_3") (pintype "passive"))
      (node (ref "R1") (pin "2") (pinfunction "2_2") (pintype "passive"))
      (node (ref "R2") (pin "2") (pinfunction "2_2") (pintype "passive"))
      (node (ref "R24") (pin "1") (pinfunction "1_1") (pintype "passive"))
      (node (ref "R34") (pin "1") (pinfunction "1_1") (pintype "passive"))
      (node (ref "R44") (pin "1") (pinfunction "1_1") (pintype "passive"))
    )
    (net (code "10") (name "DIAG") (class "Default")
      (node (ref "Q10") (pin "3") (pinfunction "D_3") (pintype "passive"))
      (node (ref "U1") (pin "36") (pinfunction "DIAG_36") (pintype "bidirectional"))
    )
    (net (code "11") (name "DIAGOUT") (class "Default")
      (node (ref "JP3") (pin "1") (pinfunction "1_1") (pintype "passive"))
      (node (ref "LED") (pin "+") (pinfunction "+_+") (pintype "passive"))
      (node (ref "R10") (pin "2") (pinfunction "2_2") (pintype "passive"))
    )
    (net (code "12") (name "GHA") (class "Default")
      (node (ref "R20") (pin "1") (pinfunction "1_1") (pintype "passive"))
      (node (ref "U1") (pin "27") (pinfunction "GHA_27") (pintype "bidirectional"))
    )
    (net (code "13") (name "GHB") (class "Default")
      (node (ref "R30") (pin "1") (pinfunction "1_1") (pintype "passive"))
      (node (ref "U1") (pin "23") (pinfunction "GHB_23") (pintype "bidirectional"))
    )
    (net (code "14") (name "GHC") (class "Default")
      (node (ref "R40") (pin "1") (pinfunction "1_1") (pintype "passive"))
      (node (ref "U1") (pin "19") (pinfunction "GHC_19") (pintype "bidirectional"))
    )
    (net (code "15") (name "GLA") (class "Default")
      (node (ref "R23") (pin "1") (pinfunction "1_1") (pintype "passive"))
      (node (ref "U1") (pin "26") (pinfunction "GLA_26") (pintype "bidirectional"))
    )
    (net (code "16") (name "GLB") (class "Default")
      (node (ref "R33") (pin "1") (pinfunction "1_1") (pintype "passive"))
      (node (ref "U1") (pin "22") (pinfunction "GLB_22") (pintype "bidirectional"))
    )
    (net (code "17") (name "GLC") (class "Default")
      (node (ref "R43") (pin "1") (pinfunction "1_1") (pintype "passive"))
      (node (ref "U1") (pin "18") (pinfunction "GLC_18") (pintype "bidirectional"))
    )
    (net (code "18") (name "GND") (class "Default")
      (node (ref "C1") (pin "1") (pinfunction "1_1") (pintype "passive"))
      (node (ref "C10") (pin "1") (pinfunction "1_1") (pintype "passive"))
      (node (ref "C11") (pin "1") (pinfunction "1_1") (pintype "passive"))
      (node (ref "C12") (pin "1") (pinfunction "1_1") (pintype "passive"))
      (node (ref "C14") (pin "1") (pinfunction "1_1") (pintype "passive"))
      (node (ref "C15") (pin "1") (pinfunction "1_1") (pintype "passive"))
      (node (ref "C16") (pin "1") (pinfunction "1_1") (pintype "passive"))
      (node (ref "C17") (pin "1") (pinfunction "1_1") (pintype "passive"))
      (node (ref "C18") (pin "1") (pinfunction "1_1") (pintype "passive"))
      (node (ref "C2") (pin "1") (pinfunction "1_1") (pintype "passive"))
      (node (ref "C4") (pin "2") (pinfunction "-_2") (pintype "bidirectional"))
      (node (ref "C5") (pin "2") (pinfunction "-_2") (pintype "bidirectional"))
      (node (ref "C50") (pin "1") (pinfunction "1_1") (pintype "passive"))
      (node (ref "C51") (pin "1") (pinfunction "1_1") (pintype "passive"))
      (node (ref "C52") (pin "1") (pinfunction "1_1") (pintype "passive"))
      (node (ref "C53") (pin "1") (pinfunction "1_1") (pintype "passive"))
      (node (ref "C6") (pin "1") (pinfunction "1_1") (pintype "passive"))
      (node (ref "C60") (pin "1") (pinfunction "1_1") (pintype "passive"))
      (node (ref "C61") (pin "2") (pinfunction "2_2") (pintype "passive"))
      (node (ref "C62") (pin "2") (pinfunction "2_2") (pintype "passive"))
      (node (ref "C7") (pin "1") (pinfunction "1_1") (pintype "passive"))
      (node (ref "D51") (pin "1") (pinfunction "A_1") (pintype "passive"))
      (node (ref "D51") (pin "2") (pinfunction "A_2") (pintype "passive"))
      (node (ref "JP1") (pin "3") (pinfunction "3_3") (pintype "bidirectional"))
      (node (ref "LED") (pin "-") (pinfunction "-_-") (pintype "passive"))
      (node (ref "R1") (pin "1") (pinfunction "1_1") (pintype "passive"))
      (node (ref "R3") (pin "2") (pinfunction "2_2") (pintype "passive"))
      (node (ref "R5") (pin "1") (pinfunction "1_1") (pintype "passive"))
      (node (ref "TVS") (pin "2") (pinfunction "A_2") (pintype "bidirectional"))
      (node (ref "TVS-") (pin "1") (pinfunction "K_1") (pintype "bidirectional"))
      (node (ref "U1") (pin "1") (pinfunction "NC_1") (pintype "bidirectional"))
      (node (ref "U1") (pin "10") (pinfunction "NC3_10") (pintype "bidirectional"))
      (node (ref "U1") (pin "15") (pinfunction "LIN_15") (pintype "bidirectional"))
      (node (ref "U1") (pin "16") (pinfunction "GND_16") (pintype "bidirectional"))
      (node (ref "U1") (pin "17") (pinfunction "GND2_17") (pintype "bidirectional"))
      (node (ref "U1") (pin "3") (pinfunction "NC2_3") (pintype "bidirectional"))
      (node (ref "U1") (pin "34") (pinfunction "IG_34") (pintype "bidirectional"))
      (node (ref "U1") (pin "37") (pinfunction "GND_37") (pintype "bidirectional"))
      (node (ref "U2") (pin "2") (pinfunction "GND_2") (pintype "bidirectional"))
      (node (ref "U3") (pin "1") (pinfunction "GND_1_1") (pintype "bidirectional"))
      (node (ref "U3") (pin "2") (pinfunction "GND_2_2") (pintype "bidirectional"))
      (node (ref "U4") (pin "7") (pinfunction "VSS_7") (pintype "power_in"))
      (node (ref "X2") (pin "4") (pinfunction "1_4") (pintype "passive"))
      (node (ref "X3") (pin "1") (pinfunction "1_1") (pintype "passive"))
    )
    (net (code "19") (name "LINUARTRXD") (class "Default")
      (node (ref "JP2") (pin "1") (pinfunction "1_1") (pintype "passive"))
      (node (ref "U4") (pin "3") (pinfunction "PD6_3") (pintype "bidirectional"))
    )
    (net (code "20") (name "LINUARTTXD") (class "Default")
      (node (ref "JP2") (pin "2") (pinfunction "2_2") (pintype "passive"))
      (node (ref "U4") (pin "2") (pinfunction "PD5_2") (pintype "bidirectional"))
    )
    (net (code "21") (name "NRST") (class "Default")
      (node (ref "JP1") (pin "4") (pinfunction "4_4") (pintype "bidirectional"))
      (node (ref "U1") (pin "9") (pinfunction "MRSTN_9") (pintype "bidirectional"))
      (node (ref "U4") (pin "4") (pinfunction "NRST_4") (pintype "bidirectional"))
    )
    (net (code "22") (name "Net-(D21-K)") (class "Default")
      (node (ref "C22") (pin "2") (pinfunction "2_2") (pintype "passive"))
      (node (ref "D21") (pin "1") (pinfunction "K_1") (pintype "bidirectional"))
      (node (ref "R22") (pin "1") (pinfunction "1_1") (pintype "passive"))
    )
    (net (code "23") (name "Net-(D22-K)") (class "Default")
      (node (ref "C23") (pin "2") (pinfunction "2_2") (pintype "passive"))
      (node (ref "D22") (pin "1") (pinfunction "K_1") (pintype "bidirectional"))
      (node (ref "R25") (pin "1") (pinfunction "1_1") (pintype "passive"))
    )
    (net (code "24") (name "Net-(D31-K)") (class "Default")
      (node (ref "C32") (pin "2") (pinfunction "2_2") (pintype "passive"))
      (node (ref "D31") (pin "1") (pinfunction "K_1") (pintype "bidirectional"))
      (node (ref "R32") (pin "1") (pinfunction "1_1") (pintype "passive"))
    )
    (net (code "25") (name "Net-(D32-K)") (class "Default")
      (node (ref "C33") (pin "2") (pinfunction "2_2") (pintype "passive"))
      (node (ref "D32") (pin "1") (pinfunction "K_1") (pintype "bidirectional"))
      (node (ref "R35") (pin "1") (pinfunction "1_1") (pintype "passive"))
    )
    (net (code "26") (name "Net-(D41-K)") (class "Default")
      (node (ref "C42") (pin "2") (pinfunction "2_2") (pintype "passive"))
      (node (ref "D41") (pin "1") (pinfunction "K_1") (pintype "bidirectional"))
      (node (ref "R42") (pin "1") (pinfunction "1_1") (pintype "passive"))
    )
    (net (code "27") (name "Net-(D42-K)") (class "Default")
      (node (ref "C43") (pin "2") (pinfunction "2_2") (pintype "passive"))
      (node (ref "D42") (pin "1") (pinfunction "K_1") (pintype "bidirectional"))
      (node (ref "R45") (pin "1") (pinfunction "1_1") (pintype "passive"))
    )
    (net (code "28") (name "Net-(L2-Pad2)") (class "Default")
      (node (ref "L2") (pin "2") (pinfunction "2_2") (pintype "bidirectional"))
      (node (ref "R4") (pin "1") (pinfunction "1_1") (pintype "passive"))
    )
    (net (code "29") (name "Net-(Q1-G)") (class "Default")
      (node (ref "Q1") (pin "4") (pinfunction "G_4") (pintype "passive"))
      (node (ref "R20") (pin "2") (pinfunction "2_2") (pintype "passive"))
      (node (ref "R21") (pin "2") (pinfunction "2_2") (pintype "passive"))
    )
    (net (code "30") (name "Net-(Q2-G)") (class "Default")
      (node (ref "Q2") (pin "4") (pinfunction "G_4") (pintype "passive"))
      (node (ref "R23") (pin "2") (pinfunction "2_2") (pintype "passive"))
      (node (ref "R24") (pin "2") (pinfunction "2_2") (pintype "passive"))
    )
    (net (code "31") (name "Net-(Q3-G)") (class "Default")
      (node (ref "Q3") (pin "4") (pinfunction "G_4") (pintype "passive"))
      (node (ref "R30") (pin "2") (pinfunction "2_2") (pintype "passive"))
      (node (ref "R31") (pin "2") (pinfunction "2_2") (pintype "passive"))
    )
    (net (code "32") (name "Net-(Q4-G)") (class "Default")
      (node (ref "Q4") (pin "4") (pinfunction "G_4") (pintype "passive"))
      (node (ref "R33") (pin "2") (pinfunction "2_2") (pintype "passive"))
      (node (ref "R34") (pin "2") (pinfunction "2_2") (pintype "passive"))
    )
    (net (code "33") (name "Net-(Q5-G)") (class "Default")
      (node (ref "Q5") (pin "4") (pinfunction "G_4") (pintype "passive"))
      (node (ref "R40") (pin "2") (pinfunction "2_2") (pintype "passive"))
      (node (ref "R41") (pin "2") (pinfunction "2_2") (pintype "passive"))
    )
    (net (code "34") (name "Net-(Q6-G)") (class "Default")
      (node (ref "Q6") (pin "4") (pinfunction "G_4") (pintype "passive"))
      (node (ref "R43") (pin "2") (pinfunction "2_2") (pintype "passive"))
      (node (ref "R44") (pin "2") (pinfunction "2_2") (pintype "passive"))
    )
    (net (code "35") (name "Net-(Q7-G)") (class "Default")
      (node (ref "Q7") (pin "1") (pinfunction "G_1") (pintype "passive"))
      (node (ref "Q8") (pin "1") (pinfunction "G_1") (pintype "passive"))
      (node (ref "U2") (pin "5") (pinfunction "GATE_5") (pintype "bidirectional"))
    )
    (net (code "36") (name "Net-(Q9-S)") (class "Default")
      (node (ref "Q9") (pin "2") (pinfunction "S_2") (pintype "passive"))
      (node (ref "R7") (pin "1") (pinfunction "1_1") (pintype "passive"))
      (node (ref "R8") (pin "1") (pinfunction "1_1") (pintype "passive"))
    )
    (net (code "37") (name "Net-(Q10-S)") (class "Default")
      (node (ref "Q10") (pin "2") (pinfunction "S_2") (pintype "passive"))
      (node (ref "R10") (pin "1") (pinfunction "1_1") (pintype "passive"))
      (node (ref "R9") (pin "1") (pinfunction "1_1") (pintype "passive"))
    )
    (net (code "38") (name "Net-(R4-Pad2)") (class "Default")
      (node (ref "R4") (pin "2") (pinfunction "2_2") (pintype "passive"))
      (node (ref "R5") (pin "2") (pinfunction "2_2") (pintype "passive"))
      (node (ref "R6") (pin "1") (pinfunction "1_1") (pintype "passive"))
    )
    (net (code "39") (name "Net-(TVS+-A)") (class "Default")
      (node (ref "TVS+") (pin "2") (pinfunction "A_2") (pintype "bidirectional"))
      (node (ref "TVS-") (pin "2") (pinfunction "A_2") (pintype "bidirectional"))
    )
    (net (code "40") (name "Net-(TVS+-K)") (class "Default")
      (node (ref "C1") (pin "2") (pinfunction "2_2") (pintype "passive"))
      (node (ref "C2") (pin "2") (pinfunction "2_2") (pintype "passive"))
      (node (ref "C3") (pin "2") (pinfunction "2_2") (pintype "passive"))
      (node (ref "L1") (pin "2") (pinfunction "2_2") (pintype "bidirectional"))
      (node (ref "Q7") (pin "2") (pinfunction "S_2") (pintype "passive"))
      (node (ref "Q7") (pin "3") (pinfunction "S_3") (pintype "passive"))
      (node (ref "Q7") (pin "4") (pinfunction "S_4") (pintype "passive"))
      (node (ref "Q7") (pin "5") (pinfunction "S_5") (pintype "passive"))
      (node (ref "Q7") (pin "6") (pinfunction "S_6") (pintype "passive"))
      (node (ref "Q7") (pin "7") (pinfunction "S_7") (pintype "passive"))
      (node (ref "Q7") (pin "8") (pinfunction "S_8") (pintype "passive"))
      (node (ref "Q8") (pin "2") (pinfunction "S_2") (pintype "passive"))
      (node (ref "Q8") (pin "3") (pinfunction "S_3") (pintype "passive"))
      (node (ref "Q8") (pin "4") (pinfunction "S_4") (pintype "passive"))
      (node (ref "Q8") (pin "5") (pinfunction "S_5") (pintype "passive"))
      (node (ref "Q8") (pin "6") (pinfunction "S_6") (pintype "passive"))
      (node (ref "Q8") (pin "7") (pinfunction "S_7") (pintype "passive"))
      (node (ref "Q8") (pin "8") (pinfunction "S_8") (pintype "passive"))
      (node (ref "TVS+") (pin "1") (pinfunction "K_1") (pintype "bidirectional"))
      (node (ref "U2") (pin "3") (pinfunction "EN_3") (pintype "bidirectional"))
      (node (ref "U2") (pin "6") (pinfunction "ANODE_6") (pintype "bidirectional"))
    )
    (net (code "41") (name "Net-(U1-CP1)") (class "Default")
      (node (ref "C13") (pin "1") (pinfunction "1_1") (pintype "passive"))
      (node (ref "U1") (pin "32") (pinfunction "CP1_32") (pintype "bidirectional"))
    )
    (net (code "42") (name "Net-(U1-CP2)") (class "Default")
      (node (ref "C13") (pin "2") (pinfunction "2_2") (pintype "passive"))
      (node (ref "U1") (pin "31") (pinfunction "CP2_31") (pintype "bidirectional"))
    )
    (net (code "43") (name "Net-(U1-VREG)") (class "Default")
      (node (ref "C16") (pin "2") (pinfunction "2_2") (pintype "passive"))
      (node (ref "C17") (pin "2") (pinfunction "2_2") (pintype "passive"))
      (node (ref "C18") (pin "2") (pinfunction "2_2") (pintype "passive"))
      (node (ref "U1") (pin "30") (pinfunction "VREG_30") (pintype "bidirectional"))
    )
    (net (code "44") (name "Net-(U2-VCAP)") (class "Default")
      (node (ref "C3") (pin "1") (pinfunction "1_1") (pintype "passive"))
      (node (ref "U2") (pin "1") (pinfunction "VCAP_1") (pintype "bidirectional"))
    )
    (net (code "45") (name "Net-(U3-OUT)") (class "Default")
      (node (ref "R11") (pin "1") (pinfunction "1_1") (pintype "passive"))
      (node (ref "U3") (pin "3") (pinfunction "OUT_3") (pintype "bidirectional"))
    )
    (net (code "46") (name "PWMIN") (class "Default")
      (node (ref "R8") (pin "2") (pinfunction "2_2") (pintype "passive"))
      (node (ref "U4") (pin "13") (pinfunction "PC3_13") (pintype "bidirectional"))
    )
    (net (code "47") (name "PWM_CMD") (class "Default")
      (node (ref "C51") (pin "2") (pinfunction "2_2") (pintype "passive"))
      (node (ref "JP3") (pin "2") (pinfunction "2_2") (pintype "passive"))
      (node (ref "Q9") (pin "3") (pinfunction "D_3") (pintype "passive"))
      (node (ref "TVS") (pin "1") (pinfunction "K_1") (pintype "bidirectional"))
    )
    (net (code "48") (name "SA") (class "Default")
      (node (ref "C20") (pin "1") (pinfunction "1_1") (pintype "passive"))
      (node (ref "C21") (pin "1") (pinfunction "1_1") (pintype "passive"))
      (node (ref "C22") (pin "1") (pinfunction "1_1") (pintype "passive"))
      (node (ref "D22") (pin "2") (pinfunction "A_2") (pintype "bidirectional"))
      (node (ref "Q1") (pin "1") (pinfunction "S_1") (pintype "passive"))
      (node (ref "Q1") (pin "2") (pinfunction "S_2") (pintype "passive"))
      (node (ref "Q1") (pin "3") (pinfunction "S_3") (pintype "passive"))
      (node (ref "Q2") (pin "5") (pinfunction "D_5") (pintype "passive"))
      (node (ref "Q2") (pin "6") (pinfunction "D_6") (pintype "passive"))
      (node (ref "Q2") (pin "7") (pinfunction "D_7") (pintype "passive"))
      (node (ref "R21") (pin "1") (pinfunction "1_1") (pintype "passive"))
      (node (ref "R25") (pin "2") (pinfunction "2_2") (pintype "passive"))
      (node (ref "U1") (pin "28") (pinfunction "SA_28") (pintype "bidirectional"))
      (node (ref "X2") (pin "1") (pinfunction "1_1") (pintype "passive"))
    )
    (net (code "49") (name "SB") (class "Default")
      (node (ref "C30") (pin "1") (pinfunction "1_1") (pintype "passive"))
      (node (ref "C31") (pin "1") (pinfunction "1_1") (pintype "passive"))
      (node (ref "C32") (pin "1") (pinfunction "1_1") (pintype "passive"))
      (node (ref "D32") (pin "2") (pinfunction "A_2") (pintype "bidirectional"))
      (node (ref "Q3") (pin "1") (pinfunction "S_1") (pintype "passive"))
      (node (ref "Q3") (pin "2") (pinfunction "S_2") (pintype "passive"))
      (node (ref "Q3") (pin "3") (pinfunction "S_3") (pintype "passive"))
      (node (ref "Q4") (pin "5") (pinfunction "D_5") (pintype "passive"))
      (node (ref "Q4") (pin "6") (pinfunction "D_6") (pintype "passive"))
      (node (ref "Q4") (pin "7") (pinfunction "D_7") (pintype "passive"))
      (node (ref "R31") (pin "1") (pinfunction "1_1") (pintype "passive"))
      (node (ref "R35") (pin "2") (pinfunction "2_2") (pintype "passive"))
      (node (ref "U1") (pin "24") (pinfunction "SB_24") (pintype "bidirectional"))
      (node (ref "X2") (pin "2") (pinfunction "1_2") (pintype "passive"))
    )
    (net (code "50") (name "SC") (class "Default")
      (node (ref "C40") (pin "1") (pinfunction "1_1") (pintype "passive"))
      (node (ref "C41") (pin "1") (pinfunction "1_1") (pintype "passive"))
      (node (ref "C42") (pin "1") (pinfunction "1_1") (pintype "passive"))
      (node (ref "D42") (pin "2") (pinfunction "A_2") (pintype "bidirectional"))
      (node (ref "Q5") (pin "1") (pinfunction "S_1") (pintype "passive"))
      (node (ref "Q5") (pin "2") (pinfunction "S_2") (pintype "passive"))
      (node (ref "Q5") (pin "3") (pinfunction "S_3") (pintype "passive"))
      (node (ref "Q6") (pin "5") (pinfunction "D_5") (pintype "passive"))
      (node (ref "Q6") (pin "6") (pinfunction "D_6") (pintype "passive"))
      (node (ref "Q6") (pin "7") (pinfunction "D_7") (pintype "passive"))
      (node (ref "R41") (pin "1") (pinfunction "1_1") (pintype "passive"))
      (node (ref "R45") (pin "2") (pinfunction "2_2") (pintype "passive"))
      (node (ref "U1") (pin "20") (pinfunction "SC_20") (pintype "bidirectional"))
      (node (ref "X2") (pin "3") (pinfunction "1_3") (pintype "passive"))
    )
    (net (code "51") (name "SPI_MISO") (class "Default")
      (node (ref "U1") (pin "8") (pinfunction "SDO_8") (pintype "bidirectional"))
      (node (ref "U4") (pin "17") (pinfunction "PC7_17") (pintype "bidirectional"))
    )
    (net (code "52") (name "SPI_MOSI") (class "Default")
      (node (ref "U1") (pin "6") (pinfunction "SDI_6") (pintype "bidirectional"))
      (node (ref "U4") (pin "16") (pinfunction "PC6_16") (pintype "bidirectional"))
    )
    (net (code "53") (name "SPI_NSS") (class "Default")
      (node (ref "U1") (pin "4") (pinfunction "STRN_4") (pintype "bidirectional"))
      (node (ref "U4") (pin "14") (pinfunction "PC4_14") (pintype "bidirectional"))
    )
    (net (code "54") (name "SPI_SCK") (class "Default")
      (node (ref "U1") (pin "5") (pinfunction "SCK_5") (pintype "bidirectional"))
      (node (ref "U4") (pin "15") (pinfunction "PC5_15") (pintype "bidirectional"))
    )
    (net (code "55") (name "SWIM") (class "Default")
      (node (ref "JP1") (pin "2") (pinfunction "2_2") (pintype "bidirectional"))
      (node (ref "U4") (pin "18") (pinfunction "PD1_18") (pintype "bidirectional"))
    )
    (net (code "56") (name "TEMPSENSOR") (class "Default")
      (node (ref "C53") (pin "2") (pinfunction "2_2") (pintype "passive"))
      (node (ref "R11") (pin "2") (pinfunction "2_2") (pintype "passive"))
      (node (ref "U4") (pin "20") (pinfunction "PD3/AIN4/TIM5_CH2/ADC_ETR_20") (pintype "bidirectional"))
    )
    (net (code "57") (name "VCAP") (class "Default")
      (node (ref "C62") (pin "1") (pinfunction "1_1") (pintype "passive"))
      (node (ref "U4") (pin "8") (pinfunction "VCAP_8") (pintype "power_in"))
    )
    (net (code "58") (name "VCC") (class "Default")
      (node (ref "C10") (pin "2") (pinfunction "2_2") (pintype "passive"))
      (node (ref "C11") (pin "2") (pinfunction "2_2") (pintype "passive"))
      (node (ref "C12") (pin "2") (pinfunction "2_2") (pintype "passive"))
      (node (ref "C24") (pin "2") (pinfunction "2_2") (pintype "passive"))
      (node (ref "C25") (pin "2") (pinfunction "2_2") (pintype "passive"))
      (node (ref "C34") (pin "2") (pinfunction "2_2") (pintype "passive"))
      (node (ref "C35") (pin "2") (pinfunction "2_2") (pintype "passive"))
      (node (ref "C4") (pin "1") (pinfunction "+_1") (pintype "bidirectional"))
      (node (ref "C44") (pin "2") (pinfunction "2_2") (pintype "passive"))
      (node (ref "C45") (pin "2") (pinfunction "2_2") (pintype "passive"))
      (node (ref "C5") (pin "1") (pinfunction "+_1") (pintype "bidirectional"))
      (node (ref "C6") (pin "2") (pinfunction "2_2") (pintype "passive"))
      (node (ref "C7") (pin "2") (pinfunction "2_2") (pintype "passive"))
      (node (ref "D21") (pin "2") (pinfunction "A_2") (pintype "bidirectional"))
      (node (ref "D31") (pin "2") (pinfunction "A_2") (pintype "bidirectional"))
      (node (ref "D41") (pin "2") (pinfunction "A_2") (pintype "bidirectional"))
      (node (ref "Q1") (pin "5") (pinfunction "D_5") (pintype "passive"))
      (node (ref "Q1") (pin "6") (pinfunction "D_6") (pintype "passive"))
      (node (ref "Q1") (pin "7") (pinfunction "D_7") (pintype "passive"))
      (node (ref "Q3") (pin "5") (pinfunction "D_5") (pintype "passive"))
      (node (ref "Q3") (pin "6") (pinfunction "D_6") (pintype "passive"))
      (node (ref "Q3") (pin "7") (pinfunction "D_7") (pintype "passive"))
      (node (ref "Q5") (pin "5") (pinfunction "D_5") (pintype "passive"))
      (node (ref "Q5") (pin "6") (pinfunction "D_6") (pintype "passive"))
      (node (ref "Q5") (pin "7") (pinfunction "D_7") (pintype "passive"))
      (node (ref "Q7") (pin "10") (pinfunction "D_10") (pintype "passive"))
      (node (ref "Q7") (pin "11") (pinfunction "D_11") (pintype "passive"))
      (node (ref "Q7") (pin "12") (pinfunction "D_12") (pintype "passive"))
      (node (ref "Q7") (pin "13") (pinfunction "D_13") (pintype "passive"))
      (node (ref "Q7") (pin "9") (pinfunction "D_9") (pintype "passive"))
      (node (ref "Q8") (pin "10") (pinfunction "D_10") (pintype "passive"))
      (node (ref "Q8") (pin "11") (pinfunction "D_11") (pintype "passive"))
      (node (ref "Q8") (pin "12") (pinfunction "D_12") (pintype "passive"))
      (node (ref "Q8") (pin "13") (pinfunction "D_13") (pintype "passive"))
      (node (ref "Q8") (pin "9") (pinfunction "D_9") (pintype "passive"))
      (node (ref "R22") (pin "2") (pinfunction "2_2") (pintype "passive"))
      (node (ref "R32") (pin "2") (pinfunction "2_2") (pintype "passive"))
      (node (ref "R42") (pin "2") (pinfunction "2_2") (pintype "passive"))
      (node (ref "U1") (pin "33") (pinfunction "VBB_33") (pintype "bidirectional"))
      (node (ref "U1") (pin "35") (pinfunction "VBRG_35") (pintype "bidirectional"))
      (node (ref "U2") (pin "4") (pinfunction "CATHODE_4") (pintype "bidirectional"))
    )
    (net (code "59") (name "VDD") (class "Default")
      (node (ref "C14") (pin "2") (pinfunction "2_2") (pintype "passive"))
      (node (ref "C15") (pin "2") (pinfunction "2_2") (pintype "passive"))
      (node (ref "C52") (pin "2") (pinfunction "2_2") (pintype "passive"))
      (node (ref "C60") (pin "2") (pinfunction "2_2") (pintype "passive"))
      (node (ref "C61") (pin "1") (pinfunction "1_1") (pintype "passive"))
      (node (ref "JP1") (pin "1") (pinfunction "1_1") (pintype "bidirectional"))
      (node (ref "Q10") (pin "1") (pinfunction "G_1") (pintype "passive"))
      (node (ref "Q9") (pin "1") (pinfunction "G_1") (pintype "passive"))
      (node (ref "R7") (pin "2") (pinfunction "2_2") (pintype "passive"))
      (node (ref "R9") (pin "2") (pinfunction "2_2") (pintype "passive"))
      (node (ref "U1") (pin "2") (pinfunction "VLR_2") (pintype "bidirectional"))
      (node (ref "U3") (pin "4") (pinfunction "VDD_1_4") (pintype "bidirectional"))
      (node (ref "U3") (pin "5") (pinfunction "VDD_2_5") (pintype "bidirectional"))
      (node (ref "U4") (pin "9") (pinfunction "VDD_9") (pintype "power_in"))
    )
    (net (code "60") (name "WDOG") (class "Default")
      (node (ref "U1") (pin "7") (pinfunction "WDOG_7") (pintype "bidirectional"))
      (node (ref "U4") (pin "10") (pinfunction "PA3_10") (pintype "bidirectional"))
    )
    (net (code "61") (name "unconnected-(U1-LRX-Pad13)") (class "Default")
      (node (ref "U1") (pin "13") (pinfunction "LRX_13") (pintype "bidirectional"))
    )
    (net (code "62") (name "unconnected-(U1-LTX-Pad14)") (class "Default")
      (node (ref "U1") (pin "14") (pinfunction "LTX_14") (pintype "bidirectional"))
    )
    (net (code "63") (name "unconnected-(U4-PA1{slash}OSCIN-Pad5)") (class "Default")
      (node (ref "U4") (pin "5") (pinfunction "PA1/OSCIN_5") (pintype "bidirectional"))
    )
    (net (code "64") (name "unconnected-(U4-PA2{slash}OSCOUT-Pad6)") (class "Default")
      (node (ref "U4") (pin "6") (pinfunction "PA2/OSCOUT_6") (pintype "bidirectional"))
    )
    (net (code "65") (name "unconnected-(U4-PB4-Pad12)") (class "Default")
      (node (ref "U4") (pin "12") (pinfunction "PB4_12") (pintype "bidirectional"))
    )
    (net (code "66") (name "unconnected-(U4-PB5-Pad11)") (class "Default")
      (node (ref "U4") (pin "11") (pinfunction "PB5_11") (pintype "bidirectional"))
    )
    (net (code "67") (name "unconnected-(U4-PD4-Pad1)") (class "Default")
      (node (ref "U4") (pin "1") (pinfunction "PD4_1") (pintype "bidirectional"))
    )
  )
)
